# tides2_v40.net
KiCad netlist of a schematic drawn in EAGLE
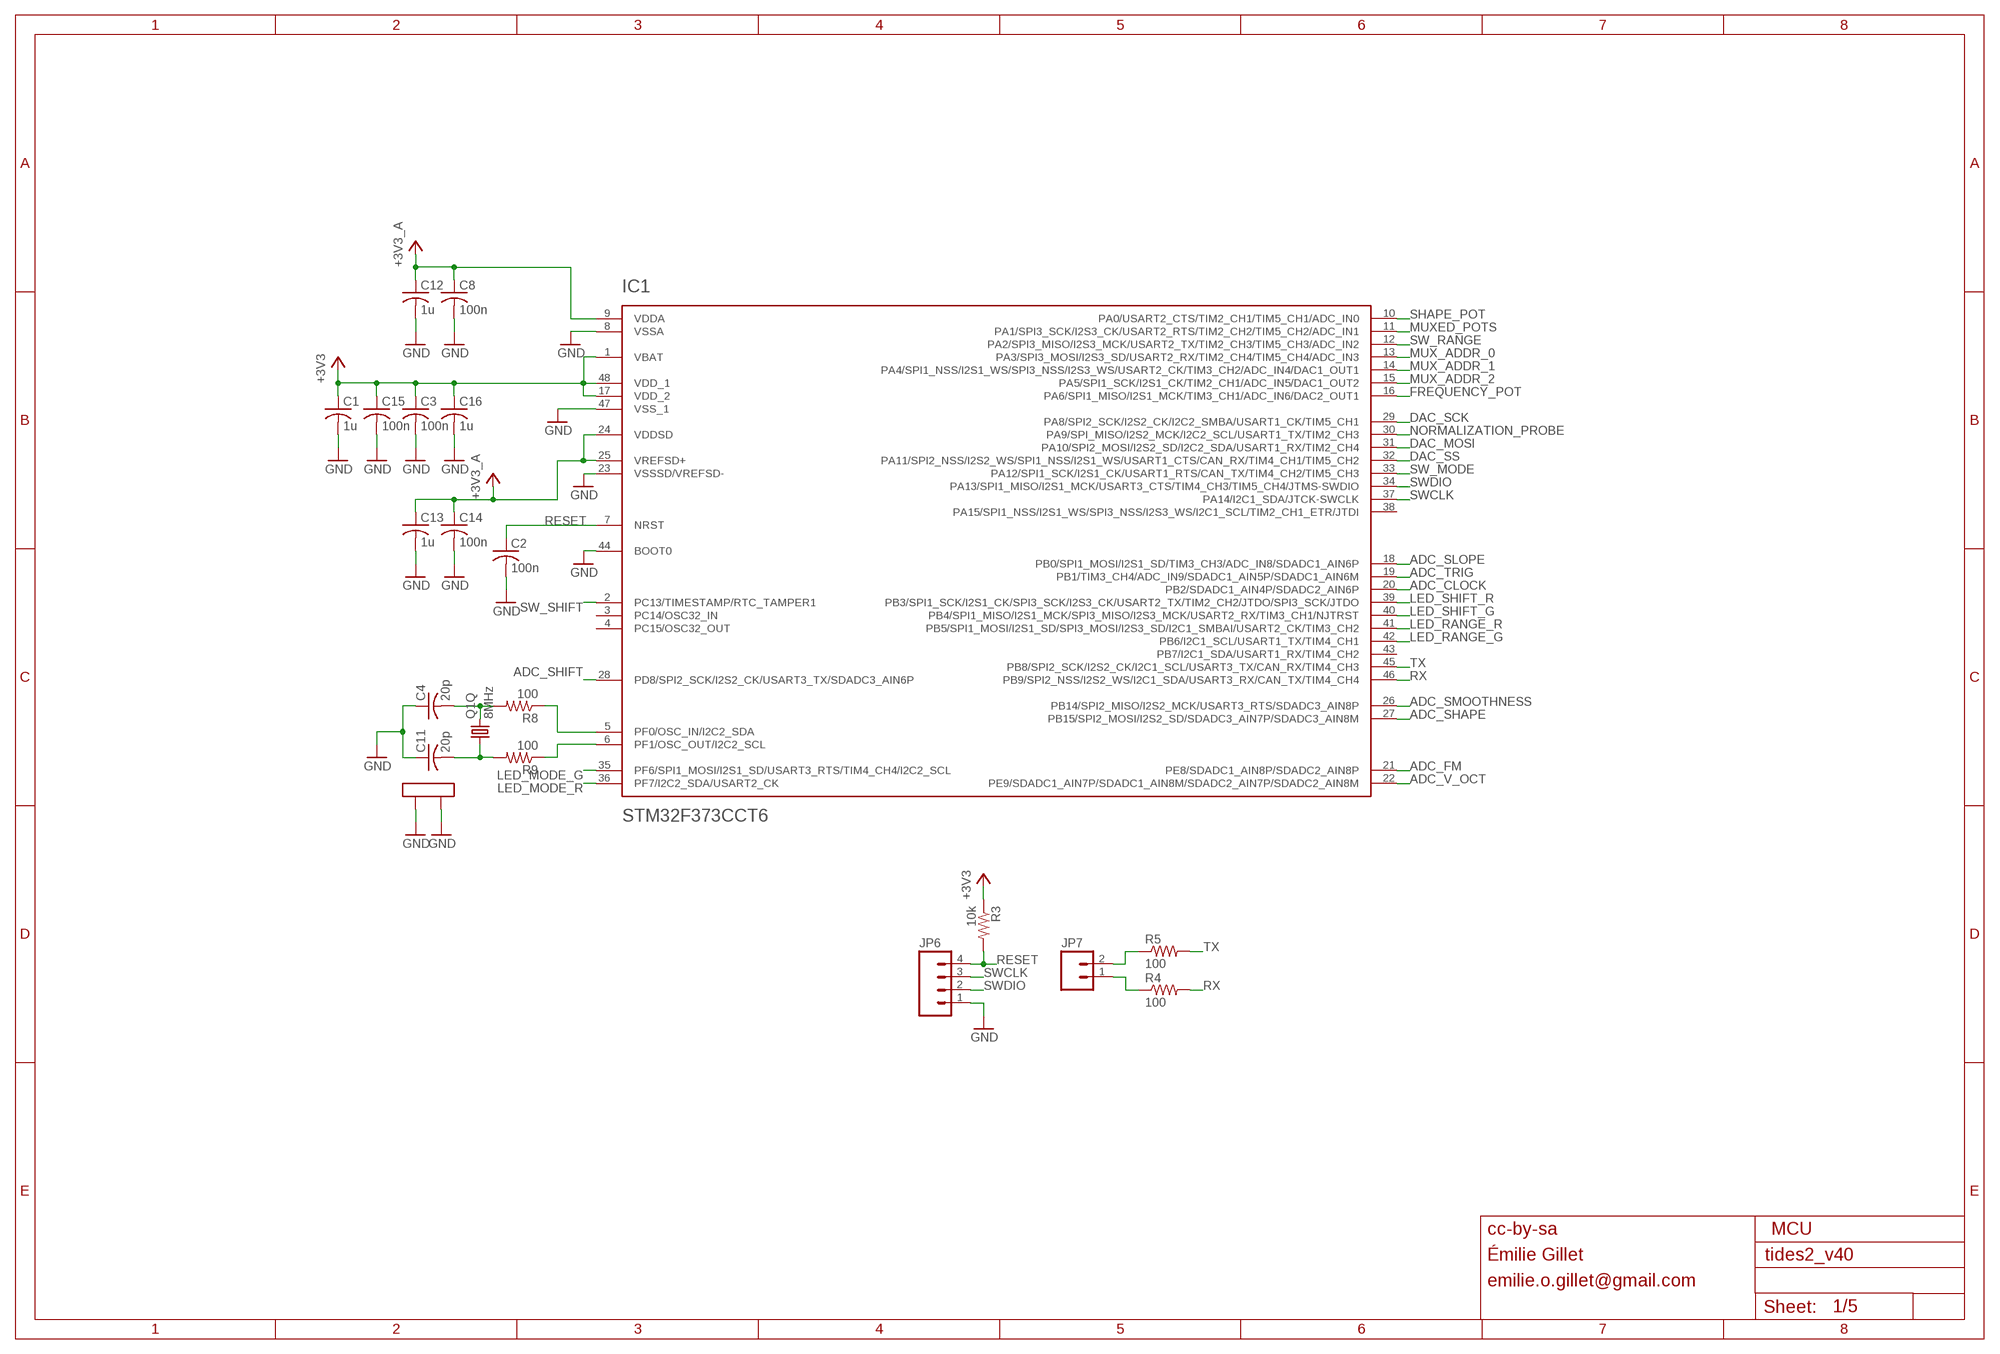
[diagram p0: schematic, sheet 1]
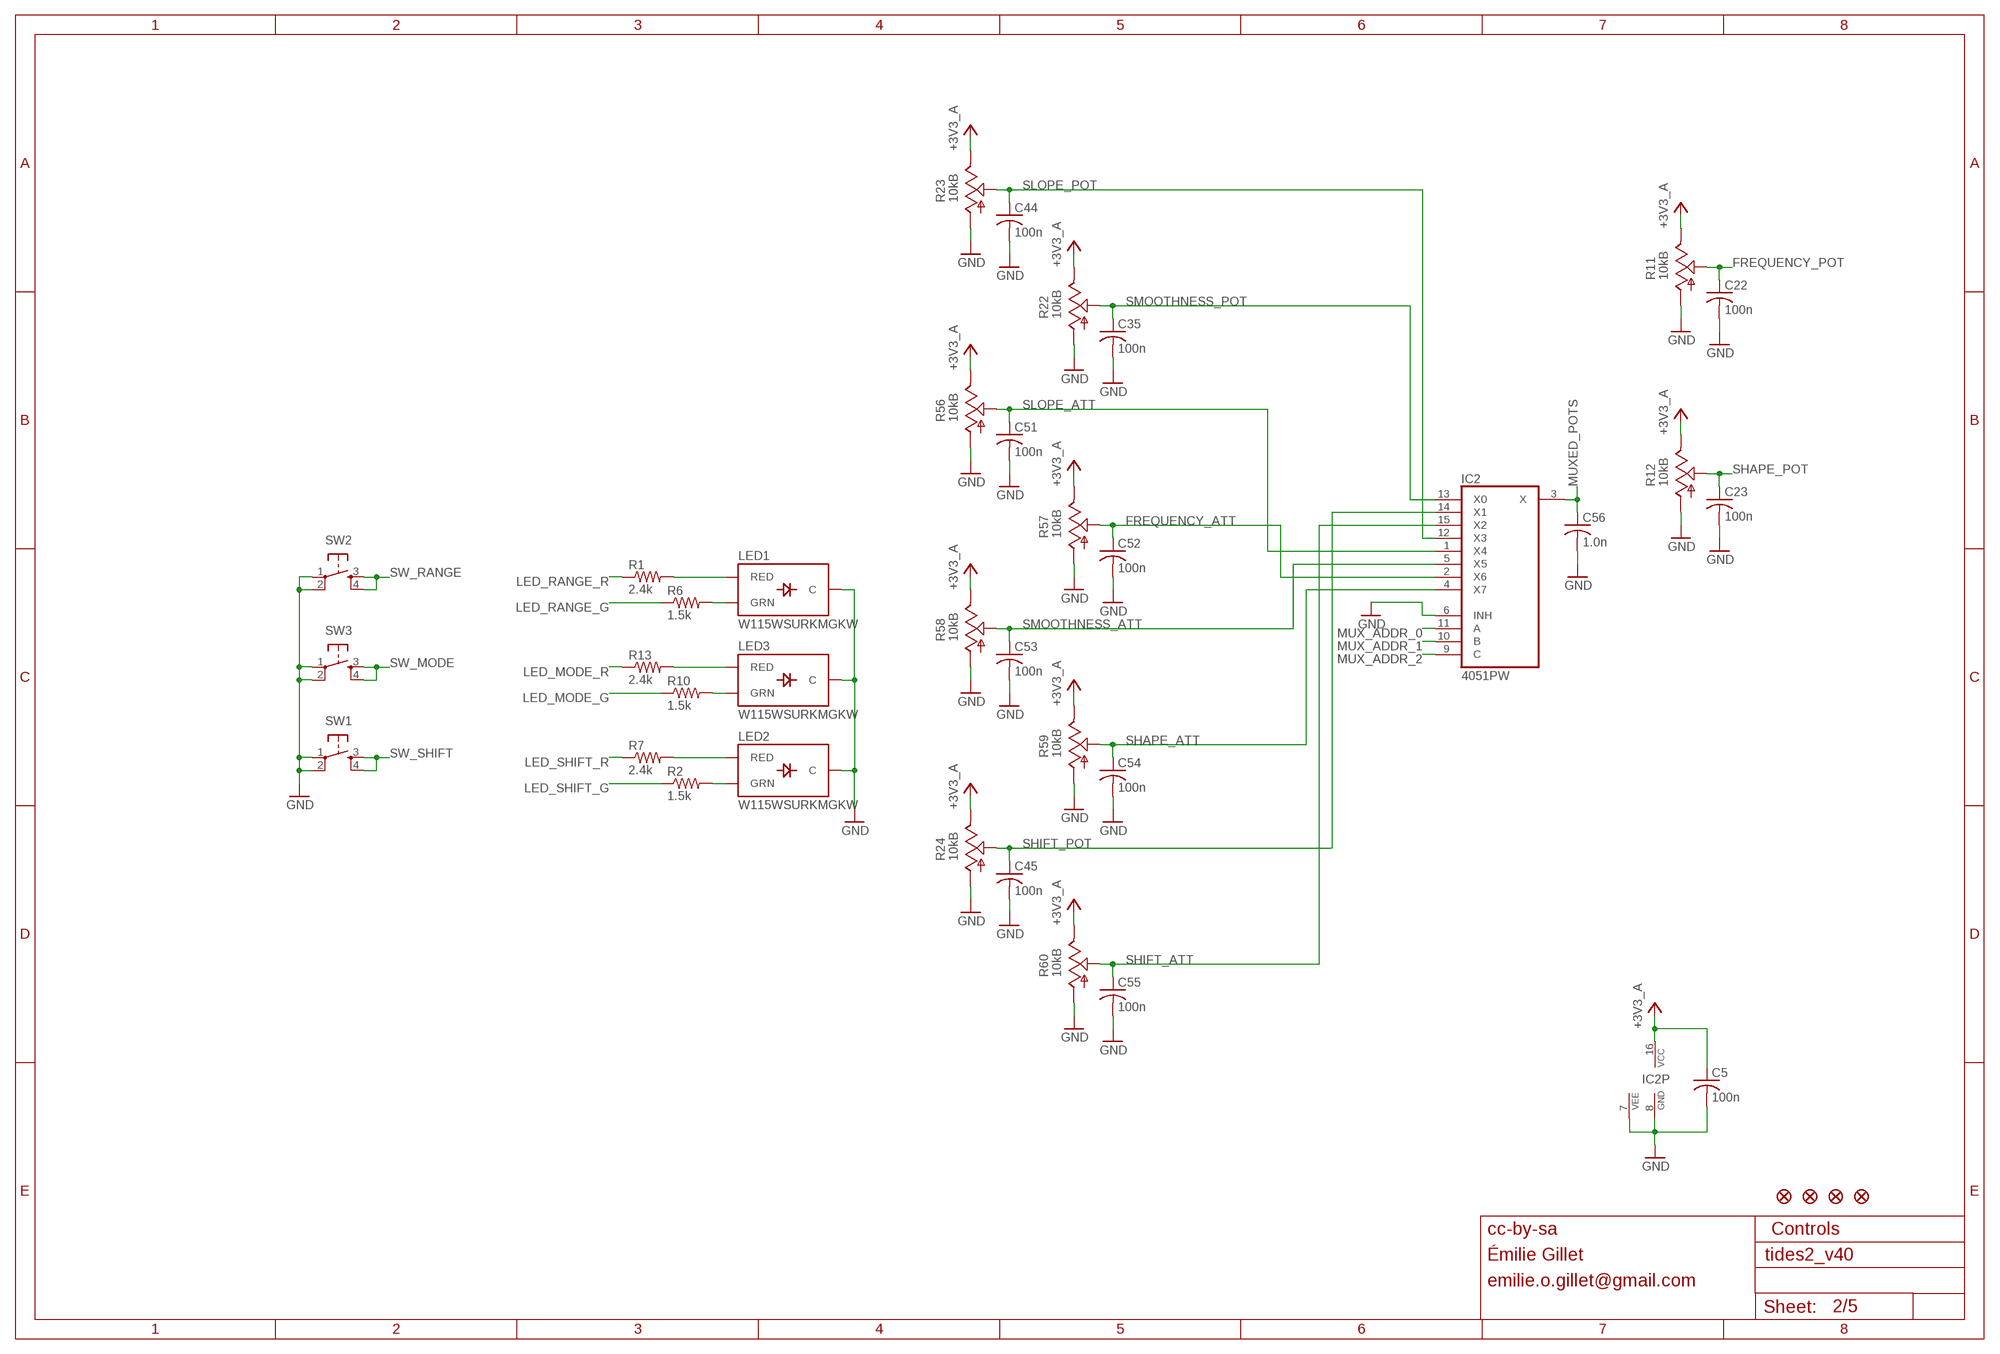
[diagram p1: schematic, sheet 2]
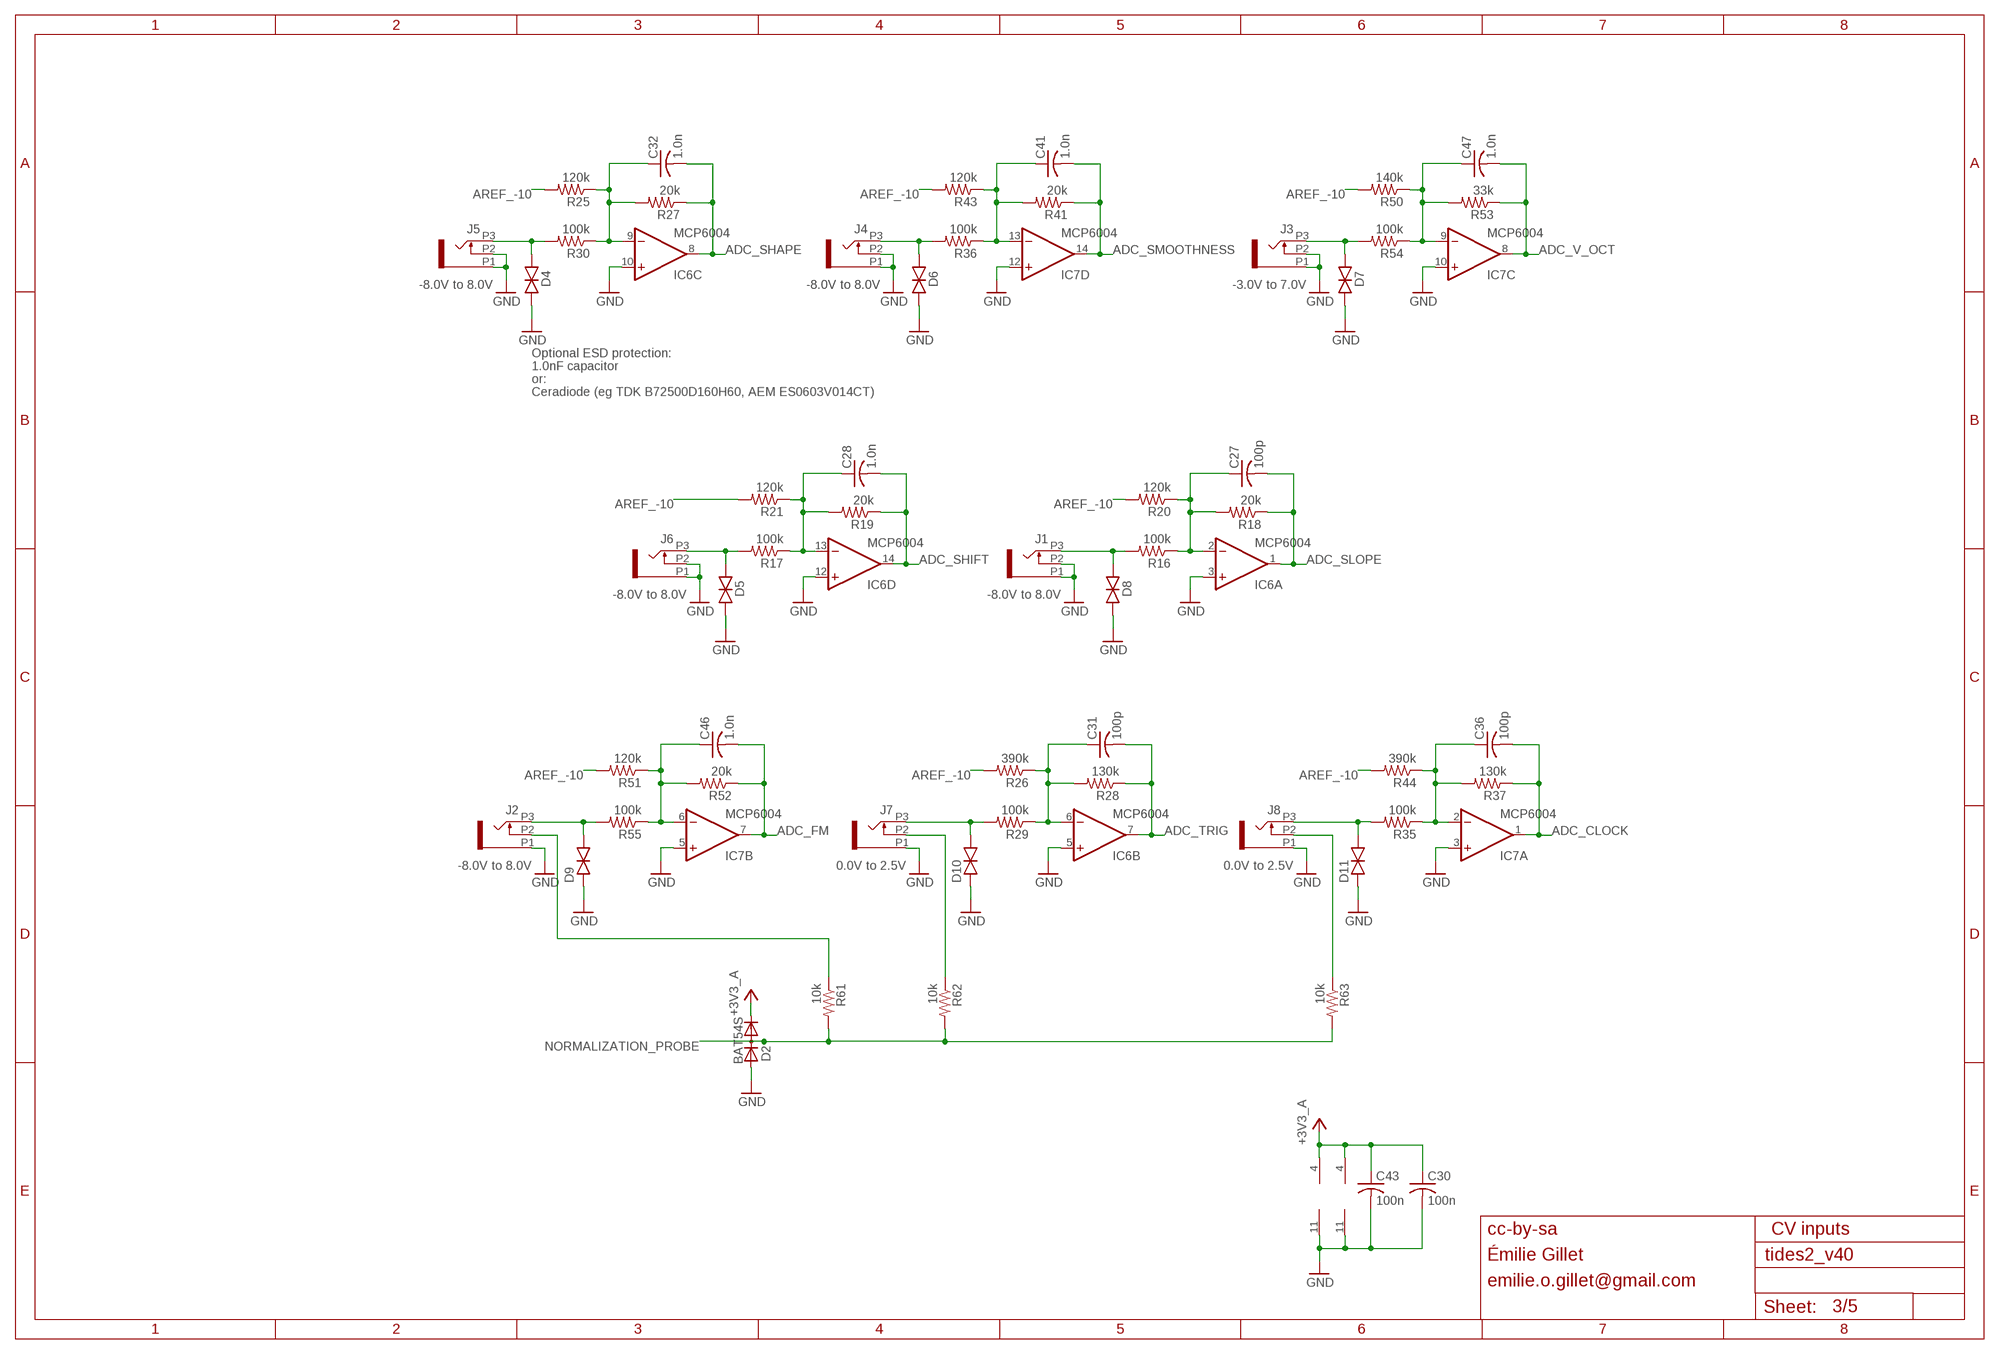
[diagram p2: schematic, sheet 3]
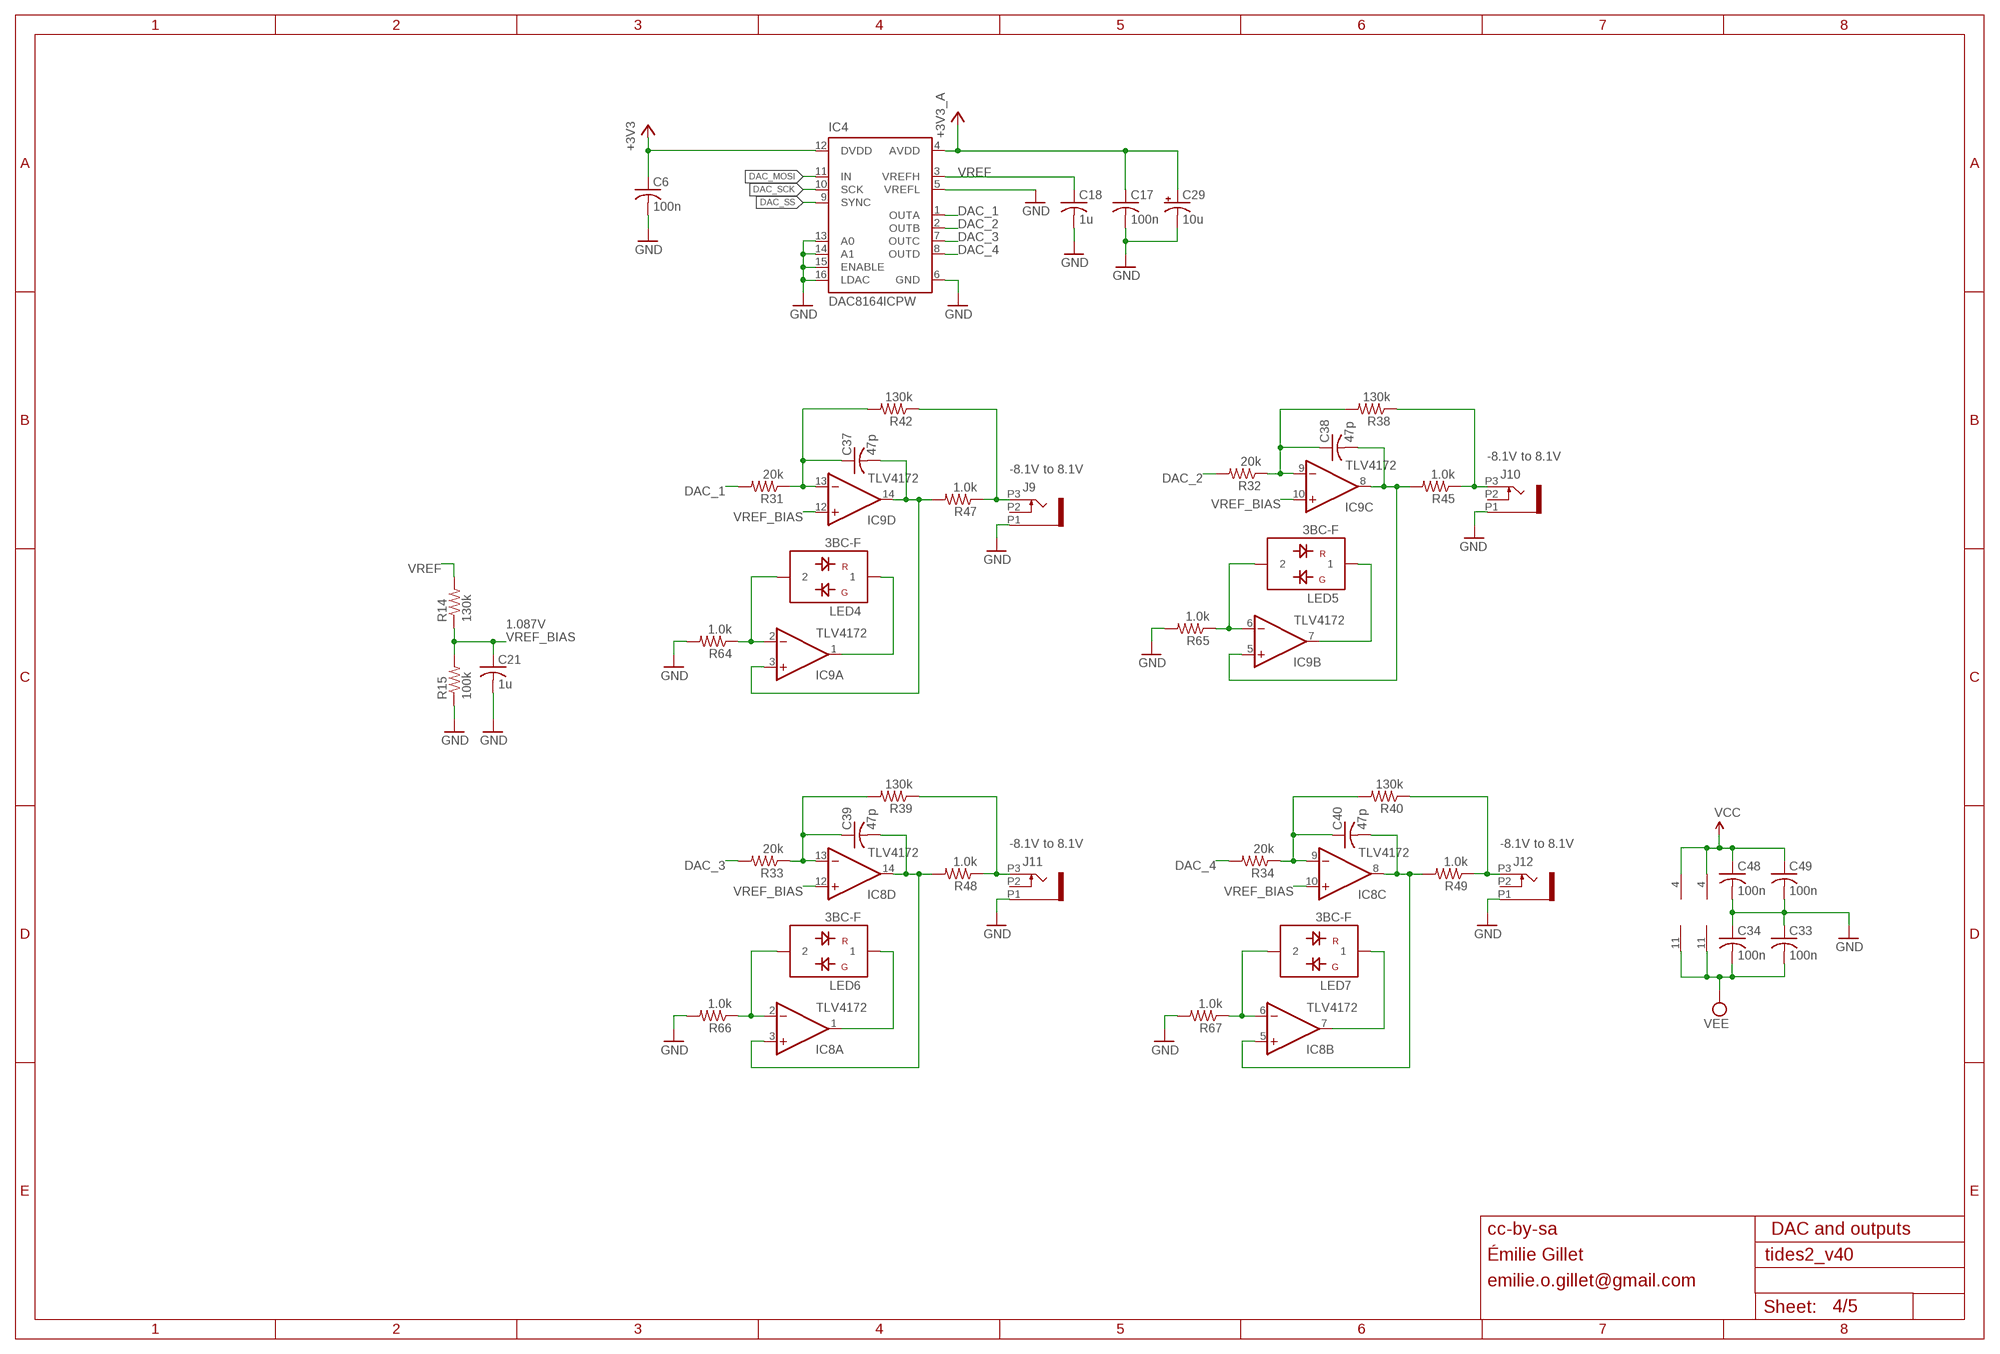
[diagram p3: schematic, sheet 4]
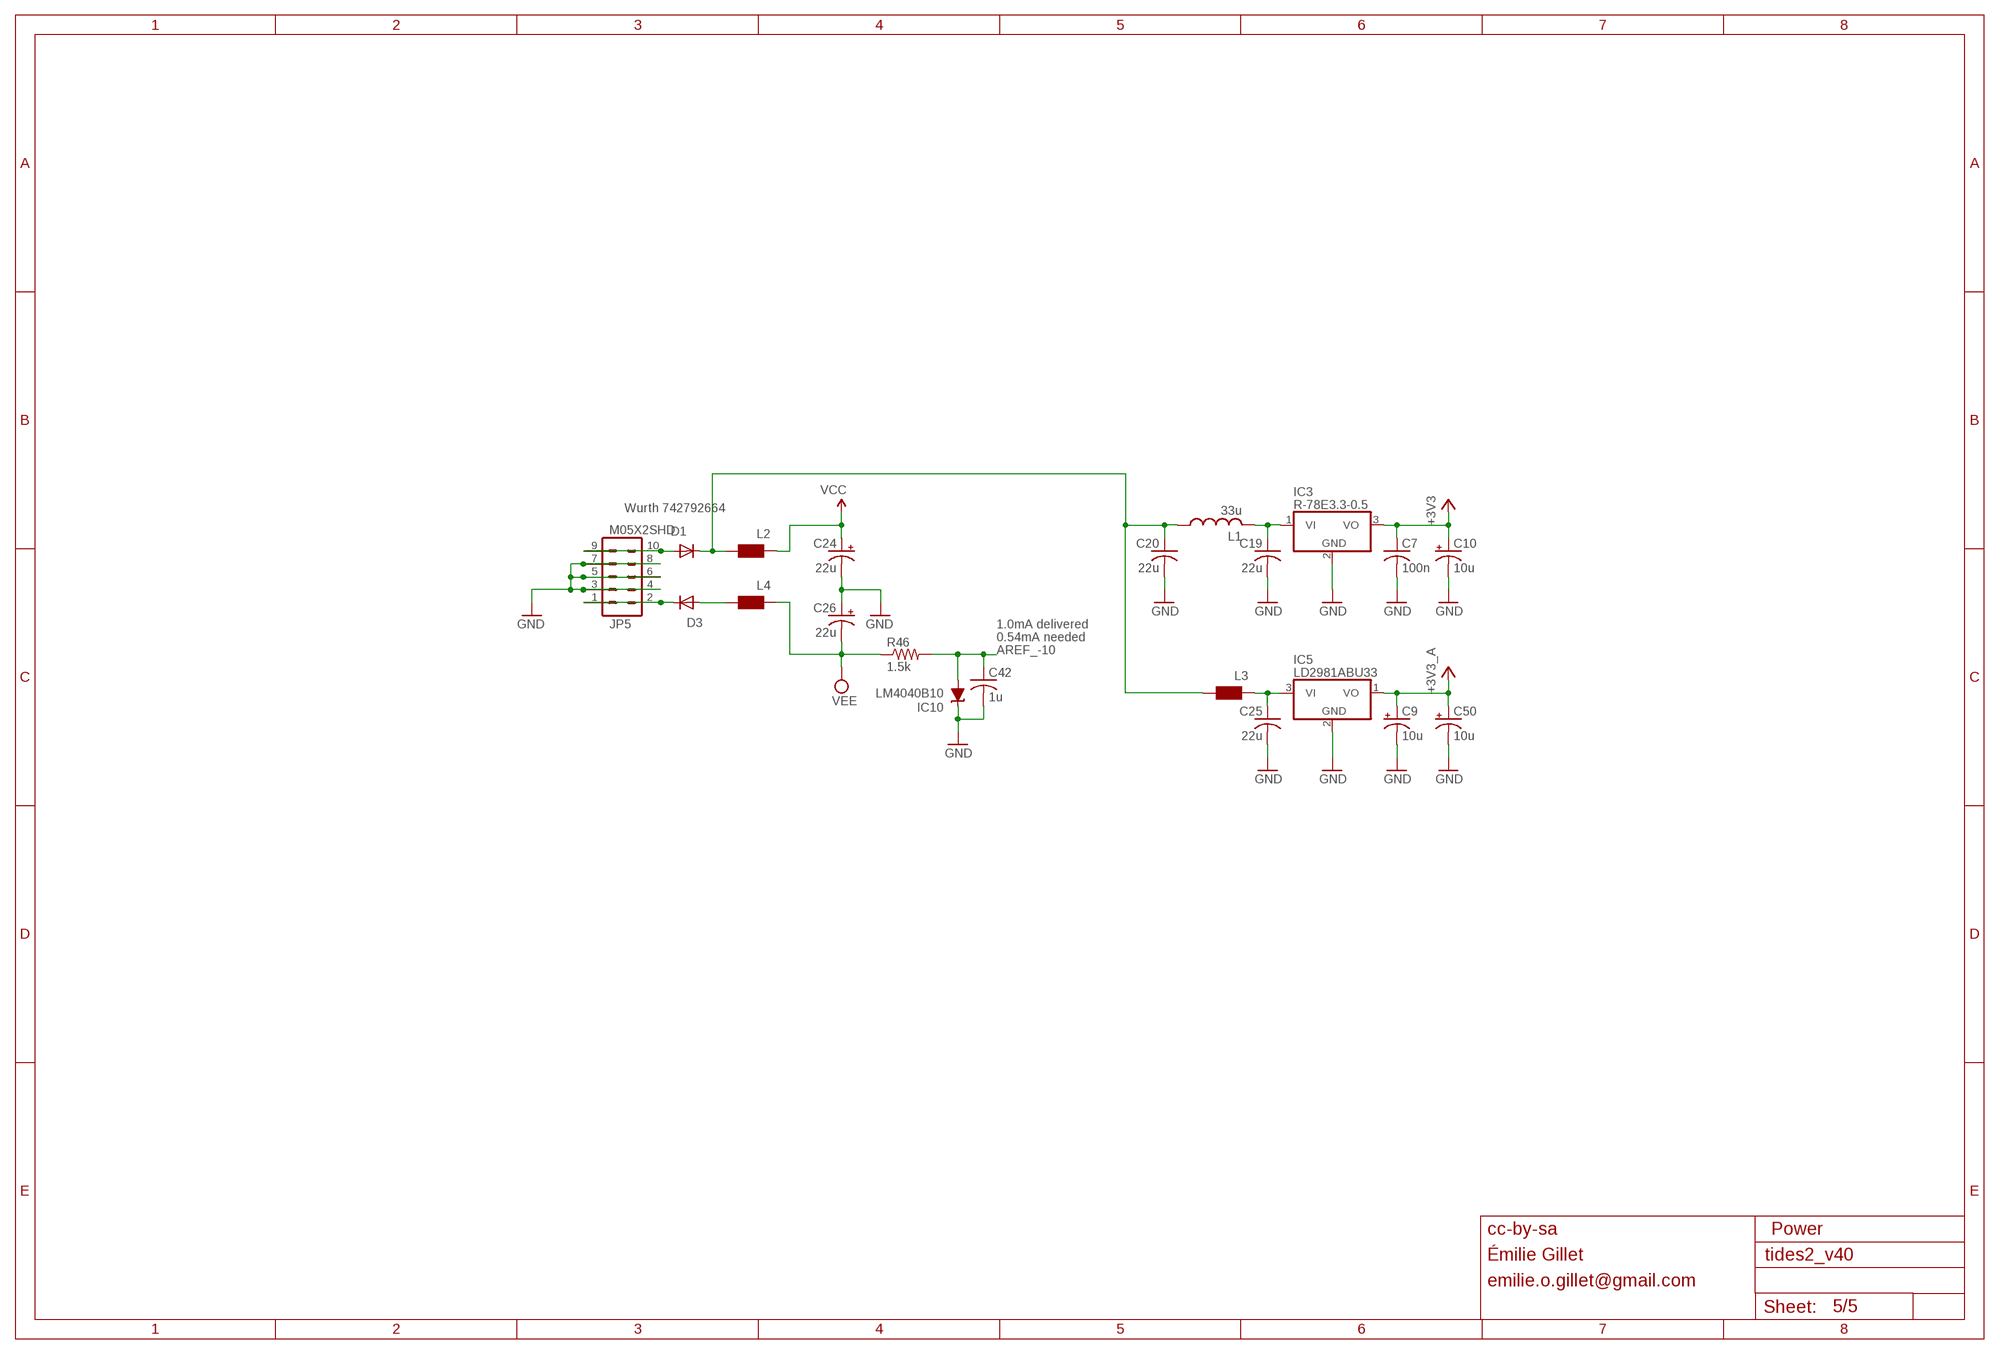
[diagram p4: schematic, sheet 5]

(export (version "E")
  (design (tool "Eeschema 10.0.6"))
  (components
    (comp (ref "C1")
      (value "1u")
      (footprint "eagle-import:C0402")
      (libsource (lib "eagle-import") (part "C-USC0402"))
    )
    (comp (ref "C2")
      (value "100n")
      (footprint "eagle-import:C0402")
      (libsource (lib "eagle-import") (part "C-USC0402"))
    )
    (comp (ref "C3")
      (value "100n")
      (footprint "eagle-import:C0402")
      (libsource (lib "eagle-import") (part "C-USC0402"))
    )
    (comp (ref "C4")
      (value "20p")
      (footprint "eagle-import:C0402")
      (libsource (lib "eagle-import") (part "C-USC0402"))
    )
    (comp (ref "C8")
      (value "100n")
      (footprint "eagle-import:C0402")
      (libsource (lib "eagle-import") (part "C-USC0402"))
    )
    (comp (ref "C11")
      (value "20p")
      (footprint "eagle-import:C0402")
      (libsource (lib "eagle-import") (part "C-USC0402"))
    )
    (comp (ref "C12")
      (value "1u")
      (footprint "eagle-import:C0402")
      (libsource (lib "eagle-import") (part "C-USC0402"))
    )
    (comp (ref "C13")
      (value "1u")
      (footprint "eagle-import:C0402")
      (libsource (lib "eagle-import") (part "C-USC0402"))
    )
    (comp (ref "C14")
      (value "100n")
      (footprint "eagle-import:C0402")
      (libsource (lib "eagle-import") (part "C-USC0402"))
    )
    (comp (ref "C15")
      (value "100n")
      (footprint "eagle-import:C0402")
      (libsource (lib "eagle-import") (part "C-USC0402"))
    )
    (comp (ref "C16")
      (value "1u")
      (footprint "eagle-import:C0402")
      (libsource (lib "eagle-import") (part "C-USC0402"))
    )
    (comp (ref "IC1")
      (value "STM32F373CCT6")
      (footprint "eagle-import:LQFP48")
      (libsource (lib "eagle-import") (part "STM32F373C"))
    )
    (comp (ref "JP6")
      (value "M04PTH")
      (footprint "eagle-import:1X04")
      (libsource (lib "eagle-import") (part "M04PTH"))
    )
    (comp (ref "JP7")
      (value "M02PTH")
      (footprint "eagle-import:1X02")
      (libsource (lib "eagle-import") (part "M02PTH"))
    )
    (comp (ref "Q1")
      (value "8MHz")
      (footprint "eagle-import:CTS406")
      (libsource (lib "eagle-import") (part "CRYSTAL"))
    )
    (comp (ref "R3")
      (value "10k")
      (footprint "eagle-import:R0402")
      (libsource (lib "eagle-import") (part "R-US_R0402"))
    )
    (comp (ref "R4")
      (value "100")
      (footprint "eagle-import:R0402")
      (libsource (lib "eagle-import") (part "R-US_R0402"))
    )
    (comp (ref "R5")
      (value "100")
      (footprint "eagle-import:R0402")
      (libsource (lib "eagle-import") (part "R-US_R0402"))
    )
    (comp (ref "R8")
      (value "100")
      (footprint "eagle-import:R0402")
      (libsource (lib "eagle-import") (part "R-US_R0402"))
    )
    (comp (ref "R9")
      (value "100")
      (footprint "eagle-import:R0402")
      (libsource (lib "eagle-import") (part "R-US_R0402"))
    )
    (comp (ref "C6")
      (value "100n")
      (footprint "eagle-import:C0402")
      (libsource (lib "eagle-import") (part "C-USC0402"))
    )
    (comp (ref "C17")
      (value "100n")
      (footprint "eagle-import:C0402")
      (libsource (lib "eagle-import") (part "C-USC0402"))
    )
    (comp (ref "C18")
      (value "1u")
      (footprint "eagle-import:C0402")
      (libsource (lib "eagle-import") (part "C-USC0402"))
    )
    (comp (ref "C21")
      (value "1u")
      (footprint "eagle-import:C0402")
      (libsource (lib "eagle-import") (part "C-USC0402"))
    )
    (comp (ref "C29")
      (value "10u")
      (footprint "eagle-import:PANASONIC_A")
      (libsource (lib "eagle-import") (part "CPOL-USA"))
    )
    (comp (ref "C33")
      (value "100n")
      (footprint "eagle-import:C0402")
      (libsource (lib "eagle-import") (part "C-USC0402"))
    )
    (comp (ref "C34")
      (value "100n")
      (footprint "eagle-import:C0402")
      (libsource (lib "eagle-import") (part "C-USC0402"))
    )
    (comp (ref "C37")
      (value "47p")
      (footprint "eagle-import:C0402")
      (libsource (lib "eagle-import") (part "C-USC0402"))
    )
    (comp (ref "C38")
      (value "47p")
      (footprint "eagle-import:C0402")
      (libsource (lib "eagle-import") (part "C-USC0402"))
    )
    (comp (ref "C39")
      (value "47p")
      (footprint "eagle-import:C0402")
      (libsource (lib "eagle-import") (part "C-USC0402"))
    )
    (comp (ref "C40")
      (value "47p")
      (footprint "eagle-import:C0402")
      (libsource (lib "eagle-import") (part "C-USC0402"))
    )
    (comp (ref "C48")
      (value "100n")
      (footprint "eagle-import:C0402")
      (libsource (lib "eagle-import") (part "C-USC0402"))
    )
    (comp (ref "C49")
      (value "100n")
      (footprint "eagle-import:C0402")
      (libsource (lib "eagle-import") (part "C-USC0402"))
    )
    (comp (ref "IC4")
      (value "DAC8164ICPW")
      (footprint "eagle-import:SOP65P640X110-16N")
      (libsource (lib "eagle-import") (part "DAC8564"))
    )
    (comp (ref "IC8")
      (value "TLV4172")
      (footprint "eagle-import:TSSOP14_065")
      (libsource (lib "eagle-import") (part "TL074PW"))
    )
    (comp (ref "IC9")
      (value "TLV4172")
      (footprint "eagle-import:TSSOP14_065")
      (libsource (lib "eagle-import") (part "TL074PW"))
    )
    (comp (ref "J9")
      (value "PJ301_THONKICONN6")
      (footprint "eagle-import:WQP_PJ_301M6")
      (libsource (lib "eagle-import") (part "PJ301_THONKICONN6"))
    )
    (comp (ref "J10")
      (value "PJ301_THONKICONN6")
      (footprint "eagle-import:WQP_PJ_301M6")
      (libsource (lib "eagle-import") (part "PJ301_THONKICONN6"))
    )
    (comp (ref "J11")
      (value "PJ301_THONKICONN6")
      (footprint "eagle-import:WQP_PJ_301M6")
      (libsource (lib "eagle-import") (part "PJ301_THONKICONN6"))
    )
    (comp (ref "J12")
      (value "PJ301_THONKICONN6")
      (footprint "eagle-import:WQP_PJ_301M6")
      (libsource (lib "eagle-import") (part "PJ301_THONKICONN6"))
    )
    (comp (ref "LED4")
      (value "3BC-F")
      (footprint "eagle-import:LED3MM")
      (libsource (lib "eagle-import") (part "LED-BICOLOR-SHARED-THROUGHHOLE"))
    )
    (comp (ref "LED5")
      (value "3BC-F")
      (footprint "eagle-import:LED3MM")
      (libsource (lib "eagle-import") (part "LED-BICOLOR-SHARED-THROUGHHOLE"))
    )
    (comp (ref "LED6")
      (value "3BC-F")
      (footprint "eagle-import:LED3MM")
      (libsource (lib "eagle-import") (part "LED-BICOLOR-SHARED-THROUGHHOLE"))
    )
    (comp (ref "LED7")
      (value "3BC-F")
      (footprint "eagle-import:LED3MM")
      (libsource (lib "eagle-import") (part "LED-BICOLOR-SHARED-THROUGHHOLE"))
    )
    (comp (ref "R14")
      (value "130k")
      (footprint "eagle-import:R0402")
      (libsource (lib "eagle-import") (part "R-US_R0402"))
    )
    (comp (ref "R15")
      (value "100k")
      (footprint "eagle-import:R0402")
      (libsource (lib "eagle-import") (part "R-US_R0402"))
    )
    (comp (ref "R31")
      (value "20k")
      (footprint "eagle-import:R0402")
      (libsource (lib "eagle-import") (part "R-US_R0402"))
    )
    (comp (ref "R32")
      (value "20k")
      (footprint "eagle-import:R0402")
      (libsource (lib "eagle-import") (part "R-US_R0402"))
    )
    (comp (ref "R33")
      (value "20k")
      (footprint "eagle-import:R0402")
      (libsource (lib "eagle-import") (part "R-US_R0402"))
    )
    (comp (ref "R34")
      (value "20k")
      (footprint "eagle-import:R0402")
      (libsource (lib "eagle-import") (part "R-US_R0402"))
    )
    (comp (ref "R38")
      (value "130k")
      (footprint "eagle-import:R0402")
      (libsource (lib "eagle-import") (part "R-US_R0402"))
    )
    (comp (ref "R39")
      (value "130k")
      (footprint "eagle-import:R0402")
      (libsource (lib "eagle-import") (part "R-US_R0402"))
    )
    (comp (ref "R40")
      (value "130k")
      (footprint "eagle-import:R0402")
      (libsource (lib "eagle-import") (part "R-US_R0402"))
    )
    (comp (ref "R42")
      (value "130k")
      (footprint "eagle-import:R0402")
      (libsource (lib "eagle-import") (part "R-US_R0402"))
    )
    (comp (ref "R45")
      (value "1.0k")
      (footprint "eagle-import:R0603")
      (libsource (lib "eagle-import") (part "R-US_R0603"))
    )
    (comp (ref "R47")
      (value "1.0k")
      (footprint "eagle-import:R0603")
      (libsource (lib "eagle-import") (part "R-US_R0603"))
    )
    (comp (ref "R48")
      (value "1.0k")
      (footprint "eagle-import:R0603")
      (libsource (lib "eagle-import") (part "R-US_R0603"))
    )
    (comp (ref "R49")
      (value "1.0k")
      (footprint "eagle-import:R0603")
      (libsource (lib "eagle-import") (part "R-US_R0603"))
    )
    (comp (ref "R64")
      (value "1.0k")
      (footprint "eagle-import:R0402")
      (libsource (lib "eagle-import") (part "R-US_R0402"))
    )
    (comp (ref "R65")
      (value "1.0k")
      (footprint "eagle-import:R0402")
      (libsource (lib "eagle-import") (part "R-US_R0402"))
    )
    (comp (ref "R66")
      (value "1.0k")
      (footprint "eagle-import:R0402")
      (libsource (lib "eagle-import") (part "R-US_R0402"))
    )
    (comp (ref "R67")
      (value "1.0k")
      (footprint "eagle-import:R0402")
      (libsource (lib "eagle-import") (part "R-US_R0402"))
    )
    (comp (ref "C27")
      (value "100p")
      (footprint "eagle-import:C0402")
      (libsource (lib "eagle-import") (part "C-USC0402"))
    )
    (comp (ref "C28")
      (value "1.0n")
      (footprint "eagle-import:C0402")
      (libsource (lib "eagle-import") (part "C-USC0402"))
    )
    (comp (ref "C30")
      (value "100n")
      (footprint "eagle-import:C0402")
      (libsource (lib "eagle-import") (part "C-USC0402"))
    )
    (comp (ref "C31")
      (value "100p")
      (footprint "eagle-import:C0402")
      (libsource (lib "eagle-import") (part "C-USC0402"))
    )
    (comp (ref "C32")
      (value "1.0n")
      (footprint "eagle-import:C0402")
      (libsource (lib "eagle-import") (part "C-USC0402"))
    )
    (comp (ref "C36")
      (value "100p")
      (footprint "eagle-import:C0402")
      (libsource (lib "eagle-import") (part "C-USC0402"))
    )
    (comp (ref "C41")
      (value "1.0n")
      (footprint "eagle-import:C0402")
      (libsource (lib "eagle-import") (part "C-USC0402"))
    )
    (comp (ref "C43")
      (value "100n")
      (footprint "eagle-import:C0402")
      (libsource (lib "eagle-import") (part "C-USC0402"))
    )
    (comp (ref "C46")
      (value "1.0n")
      (footprint "eagle-import:C0402")
      (libsource (lib "eagle-import") (part "C-USC0402"))
    )
    (comp (ref "C47")
      (value "1.0n")
      (footprint "eagle-import:C0402")
      (libsource (lib "eagle-import") (part "C-USC0402"))
    )
    (comp (ref "D2")
      (value "BAT54S")
      (footprint "eagle-import:SOT23")
      (libsource (lib "eagle-import") (part "DIODE_2CACA-SOT23"))
    )
    (comp (ref "D4")
      (value "TVS")
      (footprint "eagle-import:0603")
      (libsource (lib "eagle-import") (part "TVS"))
    )
    (comp (ref "D5")
      (value "TVS")
      (footprint "eagle-import:0603")
      (libsource (lib "eagle-import") (part "TVS"))
    )
    (comp (ref "D6")
      (value "TVS")
      (footprint "eagle-import:0603")
      (libsource (lib "eagle-import") (part "TVS"))
    )
    (comp (ref "D7")
      (value "TVS")
      (footprint "eagle-import:0603")
      (libsource (lib "eagle-import") (part "TVS"))
    )
    (comp (ref "D8")
      (value "TVS")
      (footprint "eagle-import:0603")
      (libsource (lib "eagle-import") (part "TVS"))
    )
    (comp (ref "D9")
      (value "TVS")
      (footprint "eagle-import:0603")
      (libsource (lib "eagle-import") (part "TVS"))
    )
    (comp (ref "D10")
      (value "TVS")
      (footprint "eagle-import:0603")
      (libsource (lib "eagle-import") (part "TVS"))
    )
    (comp (ref "D11")
      (value "TVS")
      (footprint "eagle-import:0603")
      (libsource (lib "eagle-import") (part "TVS"))
    )
    (comp (ref "IC6")
      (value "MCP6004")
      (footprint "eagle-import:TSSOP14_065")
      (libsource (lib "eagle-import") (part "TL074PW"))
    )
    (comp (ref "IC7")
      (value "MCP6004")
      (footprint "eagle-import:TSSOP14_065")
      (libsource (lib "eagle-import") (part "TL074PW"))
    )
    (comp (ref "J1")
      (value "PJ301_THONKICONN6")
      (footprint "eagle-import:WQP_PJ_301M6")
      (libsource (lib "eagle-import") (part "og-pj301_variations_PJ301_THONKICONN6"))
    )
    (comp (ref "J2")
      (value "PJ301_THONKICONN6")
      (footprint "eagle-import:WQP_PJ_301M6")
      (libsource (lib "eagle-import") (part "og-pj301_variations_PJ301_THONKICONN6"))
    )
    (comp (ref "J3")
      (value "PJ301_THONKICONN6")
      (footprint "eagle-import:WQP_PJ_301M6")
      (libsource (lib "eagle-import") (part "og-pj301_variations_PJ301_THONKICONN6"))
    )
    (comp (ref "J4")
      (value "PJ301_THONKICONN6")
      (footprint "eagle-import:WQP_PJ_301M6")
      (libsource (lib "eagle-import") (part "og-pj301_variations_PJ301_THONKICONN6"))
    )
    (comp (ref "J5")
      (value "PJ301_THONKICONN6")
      (footprint "eagle-import:WQP_PJ_301M6")
      (libsource (lib "eagle-import") (part "og-pj301_variations_PJ301_THONKICONN6"))
    )
    (comp (ref "J6")
      (value "PJ301_THONKICONN6")
      (footprint "eagle-import:WQP_PJ_301M6")
      (libsource (lib "eagle-import") (part "og-pj301_variations_PJ301_THONKICONN6"))
    )
    (comp (ref "J7")
      (value "PJ301_THONKICONN6")
      (footprint "eagle-import:WQP_PJ_301M6")
      (libsource (lib "eagle-import") (part "og-pj301_variations_PJ301_THONKICONN6"))
    )
    (comp (ref "J8")
      (value "PJ301_THONKICONN6")
      (footprint "eagle-import:WQP_PJ_301M6")
      (libsource (lib "eagle-import") (part "og-pj301_variations_PJ301_THONKICONN6"))
    )
    (comp (ref "R16")
      (value "100k")
      (footprint "eagle-import:R0402")
      (libsource (lib "eagle-import") (part "R-US_R0402"))
    )
    (comp (ref "R17")
      (value "100k")
      (footprint "eagle-import:R0402")
      (libsource (lib "eagle-import") (part "R-US_R0402"))
    )
    (comp (ref "R18")
      (value "20k")
      (footprint "eagle-import:R0402")
      (libsource (lib "eagle-import") (part "R-US_R0402"))
    )
    (comp (ref "R19")
      (value "20k")
      (footprint "eagle-import:R0402")
      (libsource (lib "eagle-import") (part "R-US_R0402"))
    )
    (comp (ref "R20")
      (value "120k")
      (footprint "eagle-import:R0402")
      (libsource (lib "eagle-import") (part "R-US_R0402"))
    )
    (comp (ref "R21")
      (value "120k")
      (footprint "eagle-import:R0402")
      (libsource (lib "eagle-import") (part "R-US_R0402"))
    )
    (comp (ref "R25")
      (value "120k")
      (footprint "eagle-import:R0402")
      (libsource (lib "eagle-import") (part "R-US_R0402"))
    )
    (comp (ref "R26")
      (value "390k")
      (footprint "eagle-import:R0402")
      (libsource (lib "eagle-import") (part "R-US_R0402"))
    )
    (comp (ref "R27")
      (value "20k")
      (footprint "eagle-import:R0402")
      (libsource (lib "eagle-import") (part "R-US_R0402"))
    )
    (comp (ref "R28")
      (value "130k")
      (footprint "eagle-import:R0402")
      (libsource (lib "eagle-import") (part "R-US_R0402"))
    )
    (comp (ref "R29")
      (value "100k")
      (footprint "eagle-import:R0402")
      (libsource (lib "eagle-import") (part "R-US_R0402"))
    )
    (comp (ref "R30")
      (value "100k")
      (footprint "eagle-import:R0402")
      (libsource (lib "eagle-import") (part "R-US_R0402"))
    )
    (comp (ref "R35")
      (value "100k")
      (footprint "eagle-import:R0402")
      (libsource (lib "eagle-import") (part "R-US_R0402"))
    )
    (comp (ref "R36")
      (value "100k")
      (footprint "eagle-import:R0402")
      (libsource (lib "eagle-import") (part "R-US_R0402"))
    )
    (comp (ref "R37")
      (value "130k")
      (footprint "eagle-import:R0402")
      (libsource (lib "eagle-import") (part "R-US_R0402"))
    )
    (comp (ref "R41")
      (value "20k")
      (footprint "eagle-import:R0402")
      (libsource (lib "eagle-import") (part "R-US_R0402"))
    )
    (comp (ref "R43")
      (value "120k")
      (footprint "eagle-import:R0402")
      (libsource (lib "eagle-import") (part "R-US_R0402"))
    )
    (comp (ref "R44")
      (value "390k")
      (footprint "eagle-import:R0402")
      (libsource (lib "eagle-import") (part "R-US_R0402"))
    )
    (comp (ref "R50")
      (value "140k")
      (footprint "eagle-import:R0402")
      (libsource (lib "eagle-import") (part "R-US_R0402"))
    )
    (comp (ref "R51")
      (value "120k")
      (footprint "eagle-import:R0402")
      (libsource (lib "eagle-import") (part "R-US_R0402"))
    )
    (comp (ref "R52")
      (value "20k")
      (footprint "eagle-import:R0402")
      (libsource (lib "eagle-import") (part "R-US_R0402"))
    )
    (comp (ref "R53")
      (value "33k")
      (footprint "eagle-import:R0402")
      (libsource (lib "eagle-import") (part "R-US_R0402"))
    )
    (comp (ref "R54")
      (value "100k")
      (footprint "eagle-import:R0402")
      (libsource (lib "eagle-import") (part "R-US_R0402"))
    )
    (comp (ref "R55")
      (value "100k")
      (footprint "eagle-import:R0402")
      (libsource (lib "eagle-import") (part "R-US_R0402"))
    )
    (comp (ref "R61")
      (value "10k")
      (footprint "eagle-import:R0402")
      (libsource (lib "eagle-import") (part "R-US_R0402"))
    )
    (comp (ref "R62")
      (value "10k")
      (footprint "eagle-import:R0402")
      (libsource (lib "eagle-import") (part "R-US_R0402"))
    )
    (comp (ref "R63")
      (value "10k")
      (footprint "eagle-import:R0402")
      (libsource (lib "eagle-import") (part "R-US_R0402"))
    )
    (comp (ref "C7")
      (value "100n")
      (footprint "eagle-import:C0402")
      (libsource (lib "eagle-import") (part "C-USC0402"))
    )
    (comp (ref "C9")
      (value "10u")
      (footprint "eagle-import:PANASONIC_A")
      (libsource (lib "eagle-import") (part "CPOL-USA"))
    )
    (comp (ref "C10")
      (value "10u")
      (footprint "eagle-import:PANASONIC_A")
      (libsource (lib "eagle-import") (part "CPOL-USA"))
    )
    (comp (ref "C19")
      (value "22u")
      (footprint "eagle-import:C1206")
      (libsource (lib "eagle-import") (part "C-USC1206"))
    )
    (comp (ref "C20")
      (value "22u")
      (footprint "eagle-import:C1206")
      (libsource (lib "eagle-import") (part "C-USC1206"))
    )
    (comp (ref "C24")
      (value "22u")
      (footprint "eagle-import:PANASONIC_B")
      (libsource (lib "eagle-import") (part "CPOL-USB"))
    )
    (comp (ref "C25")
      (value "22u")
      (footprint "eagle-import:C1206")
      (libsource (lib "eagle-import") (part "C-USC1206"))
    )
    (comp (ref "C26")
      (value "22u")
      (footprint "eagle-import:PANASONIC_B")
      (libsource (lib "eagle-import") (part "CPOL-USB"))
    )
    (comp (ref "C42")
      (value "1u")
      (footprint "eagle-import:C0402")
      (libsource (lib "eagle-import") (part "C-USC0402"))
    )
    (comp (ref "C50")
      (value "10u")
      (footprint "eagle-import:PANASONIC_A")
      (libsource (lib "eagle-import") (part "CPOL-USA"))
    )
    (comp (ref "D1")
      (value "1N5819HW")
      (footprint "eagle-import:SOD123")
      (libsource (lib "eagle-import") (part "DIODE-SOD123"))
    )
    (comp (ref "D3")
      (value "1N5819HW")
      (footprint "eagle-import:SOD123")
      (libsource (lib "eagle-import") (part "DIODE-SOD123"))
    )
    (comp (ref "IC3")
      (value "R-78E3.3-0.5")
      (footprint "eagle-import:WE78")
      (libsource (lib "eagle-import") (part "WE173950378"))
    )
    (comp (ref "IC5")
      (value "LD2981ABU33")
      (footprint "eagle-import:SOT89")
      (libsource (lib "eagle-import") (part "LD2981ABU"))
    )
    (comp (ref "IC10")
      (value "LM4040B10")
      (footprint "eagle-import:DBZ_R-PDSO-G3")
      (libsource (lib "eagle-import") (part "LM4041DBZB12"))
    )
    (comp (ref "JP5")
      (value "M05X2SHD")
      (footprint "eagle-import:2X5-SHROUDED")
      (libsource (lib "eagle-import") (part "M05X2SHD"))
    )
    (comp (ref "L1")
      (value "33u")
      (footprint "eagle-import:L2012C")
      (libsource (lib "eagle-import") (part "L-USL2012C"))
    )
    (comp (ref "L2")
      (value "WE-CBF_0603")
      (footprint "eagle-import:0603")
      (libsource (lib "eagle-import") (part "WE-CBF_0603"))
    )
    (comp (ref "L3")
      (value "WE-CBF_0603")
      (footprint "eagle-import:0603")
      (libsource (lib "eagle-import") (part "WE-CBF_0603"))
    )
    (comp (ref "L4")
      (value "WE-CBF_0603")
      (footprint "eagle-import:0603")
      (libsource (lib "eagle-import") (part "WE-CBF_0603"))
    )
    (comp (ref "R46")
      (value "1.5k")
      (footprint "eagle-import:R0402")
      (libsource (lib "eagle-import") (part "R-US_R0402"))
    )
    (comp (ref "C5")
      (value "100n")
      (footprint "eagle-import:C0402")
      (libsource (lib "eagle-import") (part "C-USC0402"))
    )
    (comp (ref "C22")
      (value "100n")
      (footprint "eagle-import:C0402")
      (libsource (lib "eagle-import") (part "C-USC0402"))
    )
    (comp (ref "C23")
      (value "100n")
      (footprint "eagle-import:C0402")
      (libsource (lib "eagle-import") (part "C-USC0402"))
    )
    (comp (ref "C35")
      (value "100n")
      (footprint "eagle-import:C0402")
      (libsource (lib "eagle-import") (part "C-USC0402"))
    )
    (comp (ref "C44")
      (value "100n")
      (footprint "eagle-import:C0402")
      (libsource (lib "eagle-import") (part "C-USC0402"))
    )
    (comp (ref "C45")
      (value "100n")
      (footprint "eagle-import:C0402")
      (libsource (lib "eagle-import") (part "C-USC0402"))
    )
    (comp (ref "C51")
      (value "100n")
      (footprint "eagle-import:C0402")
      (libsource (lib "eagle-import") (part "C-USC0402"))
    )
    (comp (ref "C52")
      (value "100n")
      (footprint "eagle-import:C0402")
      (libsource (lib "eagle-import") (part "C-USC0402"))
    )
    (comp (ref "C53")
      (value "100n")
      (footprint "eagle-import:C0402")
      (libsource (lib "eagle-import") (part "C-USC0402"))
    )
    (comp (ref "C54")
      (value "100n")
      (footprint "eagle-import:C0402")
      (libsource (lib "eagle-import") (part "C-USC0402"))
    )
    (comp (ref "C55")
      (value "100n")
      (footprint "eagle-import:C0402")
      (libsource (lib "eagle-import") (part "C-USC0402"))
    )
    (comp (ref "C56")
      (value "1.0n")
      (footprint "eagle-import:C0402")
      (libsource (lib "eagle-import") (part "C-USC0402"))
    )
    (comp (ref "IC2")
      (value "4051PW")
      (footprint "eagle-import:TSSOP16_065")
      (libsource (lib "eagle-import") (part "4051PW"))
    )
    (comp (ref "JP1")
      (value "FIDUCIAL1X2")
      (footprint "eagle-import:FIDUCIAL-1X2")
      (libsource (lib "eagle-import") (part "FIDUCIAL1X2"))
    )
    (comp (ref "JP2")
      (value "FIDUCIAL1X2")
      (footprint "eagle-import:FIDUCIAL-1X2")
      (libsource (lib "eagle-import") (part "FIDUCIAL1X2"))
    )
    (comp (ref "JP3")
      (value "FIDUCIAL1X2")
      (footprint "eagle-import:FIDUCIAL-1X2")
      (libsource (lib "eagle-import") (part "FIDUCIAL1X2"))
    )
    (comp (ref "JP4")
      (value "FIDUCIAL1X2")
      (footprint "eagle-import:FIDUCIAL-1X2")
      (libsource (lib "eagle-import") (part "FIDUCIAL1X2"))
    )
    (comp (ref "LED1")
      (value "W115WSURKMGKW")
      (footprint "eagle-import:LED-BICOLOR-THROUGHHOLE-2.54")
      (libsource (lib "eagle-import") (part "LED-BICOLOR-THROUGHHOLE2.54"))
    )
    (comp (ref "LED2")
      (value "W115WSURKMGKW")
      (footprint "eagle-import:LED-BICOLOR-THROUGHHOLE-2.54")
      (libsource (lib "eagle-import") (part "LED-BICOLOR-THROUGHHOLE2.54"))
    )
    (comp (ref "LED3")
      (value "W115WSURKMGKW")
      (footprint "eagle-import:LED-BICOLOR-THROUGHHOLE-2.54")
      (libsource (lib "eagle-import") (part "LED-BICOLOR-THROUGHHOLE2.54"))
    )
    (comp (ref "R1")
      (value "2.4k")
      (footprint "eagle-import:R0402")
      (libsource (lib "eagle-import") (part "R-US_R0402"))
    )
    (comp (ref "R2")
      (value "1.5k")
      (footprint "eagle-import:R0402")
      (libsource (lib "eagle-import") (part "R-US_R0402"))
    )
    (comp (ref "R6")
      (value "1.5k")
      (footprint "eagle-import:R0402")
      (libsource (lib "eagle-import") (part "R-US_R0402"))
    )
    (comp (ref "R7")
      (value "2.4k")
      (footprint "eagle-import:R0402")
      (libsource (lib "eagle-import") (part "R-US_R0402"))
    )
    (comp (ref "R10")
      (value "1.5k")
      (footprint "eagle-import:R0402")
      (libsource (lib "eagle-import") (part "R-US_R0402"))
    )
    (comp (ref "R11")
      (value "10kB")
      (footprint "eagle-import:ALPS_POT_VERTICAL_PS")
      (libsource (lib "eagle-import") (part "POT_USVERTICAL_PS"))
    )
    (comp (ref "R12")
      (value "10kB")
      (footprint "eagle-import:ALPS_POT_VERTICAL_PS")
      (libsource (lib "eagle-import") (part "POT_USVERTICAL_PS"))
    )
    (comp (ref "R13")
      (value "2.4k")
      (footprint "eagle-import:R0402")
      (libsource (lib "eagle-import") (part "R-US_R0402"))
    )
    (comp (ref "R22")
      (value "10kB")
      (footprint "eagle-import:ALPS_POT_VERTICAL_PS")
      (libsource (lib "eagle-import") (part "POT_USVERTICAL_PS"))
    )
    (comp (ref "R23")
      (value "10kB")
      (footprint "eagle-import:ALPS_POT_VERTICAL_PS")
      (libsource (lib "eagle-import") (part "POT_USVERTICAL_PS"))
    )
    (comp (ref "R24")
      (value "10kB")
      (footprint "eagle-import:ALPS_POT_VERTICAL_PS")
      (libsource (lib "eagle-import") (part "POT_USVERTICAL_PS"))
    )
    (comp (ref "R56")
      (value "10kB")
      (footprint "eagle-import:ALPS_POT_VERTICAL")
      (libsource (lib "eagle-import") (part "POT_USVERTICAL"))
    )
    (comp (ref "R57")
      (value "10kB")
      (footprint "eagle-import:ALPS_POT_VERTICAL")
      (libsource (lib "eagle-import") (part "POT_USVERTICAL"))
    )
    (comp (ref "R58")
      (value "10kB")
      (footprint "eagle-import:ALPS_POT_VERTICAL")
      (libsource (lib "eagle-import") (part "POT_USVERTICAL"))
    )
    (comp (ref "R59")
      (value "10kB")
      (footprint "eagle-import:ALPS_POT_VERTICAL")
      (libsource (lib "eagle-import") (part "POT_USVERTICAL"))
    )
    (comp (ref "R60")
      (value "10kB")
      (footprint "eagle-import:ALPS_POT_VERTICAL")
      (libsource (lib "eagle-import") (part "POT_USVERTICAL"))
    )
    (comp (ref "SW1")
      (value "TAC_SWITCHPTH")
      (footprint "eagle-import:TACTILE-PTH")
      (libsource (lib "eagle-import") (part "TAC_SWITCHPTH"))
    )
    (comp (ref "SW2")
      (value "TAC_SWITCHPTH")
      (footprint "eagle-import:TACTILE-PTH")
      (libsource (lib "eagle-import") (part "TAC_SWITCHPTH"))
    )
    (comp (ref "SW3")
      (value "TAC_SWITCHPTH")
      (footprint "eagle-import:TACTILE-PTH")
      (libsource (lib "eagle-import") (part "TAC_SWITCHPTH"))
    )
  )
  (nets
    (net (code "1") (name "+3V3") (class "Default")
      (node (ref "C1") (pin "1") (pinfunction "1_1") (pintype "passive"))
      (node (ref "C10") (pin "+") (pinfunction "+_+") (pintype "passive"))
      (node (ref "C15") (pin "1") (pinfunction "1_1") (pintype "passive"))
      (node (ref "C16") (pin "1") (pinfunction "1_1") (pintype "passive"))
      (node (ref "C3") (pin "1") (pinfunction "1_1") (pintype "passive"))
      (node (ref "C6") (pin "1") (pinfunction "1_1") (pintype "passive"))
      (node (ref "C7") (pin "1") (pinfunction "1_1") (pintype "passive"))
      (node (ref "IC1") (pin "1") (pinfunction "VBAT_1") (pintype "power_in"))
      (node (ref "IC1") (pin "17") (pinfunction "VDD_2_17") (pintype "power_in"))
      (node (ref "IC1") (pin "48") (pinfunction "VDD_1_48") (pintype "power_in"))
      (node (ref "IC3") (pin "3") (pinfunction "VO_3") (pintype "passive"))
      (node (ref "IC4") (pin "12") (pinfunction "DVDD_12") (pintype "power_in"))
      (node (ref "R3") (pin "1") (pinfunction "1_1") (pintype "passive"))
    )
    (net (code "2") (name "+3V3_A") (class "Default")
      (node (ref "C12") (pin "1") (pinfunction "1_1") (pintype "passive"))
      (node (ref "C13") (pin "1") (pinfunction "1_1") (pintype "passive"))
      (node (ref "C14") (pin "1") (pinfunction "1_1") (pintype "passive"))
      (node (ref "C17") (pin "1") (pinfunction "1_1") (pintype "passive"))
      (node (ref "C29") (pin "+") (pinfunction "+_+") (pintype "passive"))
      (node (ref "C30") (pin "1") (pinfunction "1_1") (pintype "passive"))
      (node (ref "C43") (pin "1") (pinfunction "1_1") (pintype "passive"))
      (node (ref "C5") (pin "1") (pinfunction "1_1") (pintype "passive"))
      (node (ref "C50") (pin "+") (pinfunction "+_+") (pintype "passive"))
      (node (ref "C8") (pin "1") (pinfunction "1_1") (pintype "passive"))
      (node (ref "C9") (pin "+") (pinfunction "+_+") (pintype "passive"))
      (node (ref "D2") (pin "2") (pinfunction "C_2") (pintype "passive"))
      (node (ref "IC1") (pin "24") (pinfunction "VDDSD_24") (pintype "power_in"))
      (node (ref "IC1") (pin "25") (pinfunction "VREFSD+_25") (pintype "power_in"))
      (node (ref "IC1") (pin "9") (pinfunction "VDDA_9") (pintype "power_in"))
      (node (ref "IC2") (pin "16") (pinfunction "VCC_16") (pintype "power_in"))
      (node (ref "IC4") (pin "4") (pinfunction "AVDD_4") (pintype "power_in"))
      (node (ref "IC5") (pin "1") (pinfunction "VO_1") (pintype "passive"))
      (node (ref "IC6") (pin "4") (pinfunction "V+_4") (pintype "power_in"))
      (node (ref "IC7") (pin "4") (pinfunction "V+_4") (pintype "power_in"))
      (node (ref "R11") (pin "P$1") (pinfunction "E_P$1") (pintype "passive"))
      (node (ref "R12") (pin "P$1") (pinfunction "E_P$1") (pintype "passive"))
      (node (ref "R22") (pin "P$1") (pinfunction "E_P$1") (pintype "passive"))
      (node (ref "R23") (pin "P$1") (pinfunction "E_P$1") (pintype "passive"))
      (node (ref "R24") (pin "P$1") (pinfunction "E_P$1") (pintype "passive"))
      (node (ref "R56") (pin "P$1") (pinfunction "E_P$1") (pintype "passive"))
      (node (ref "R57") (pin "P$1") (pinfunction "E_P$1") (pintype "passive"))
      (node (ref "R58") (pin "P$1") (pinfunction "E_P$1") (pintype "passive"))
      (node (ref "R59") (pin "P$1") (pinfunction "E_P$1") (pintype "passive"))
      (node (ref "R60") (pin "P$1") (pinfunction "E_P$1") (pintype "passive"))
    )
    (net (code "3") (name "ADC_CLOCK") (class "Default")
      (node (ref "C36") (pin "2") (pinfunction "2_2") (pintype "passive"))
      (node (ref "IC1") (pin "20") (pinfunction "PB2/SDADC1_AIN4P/SDADC2_AIN6P_20") (pintype "bidirectional"))
      (node (ref "IC7") (pin "1") (pinfunction "OUT_1") (pintype "output"))
      (node (ref "R37") (pin "1") (pinfunction "1_1") (pintype "passive"))
    )
    (net (code "4") (name "ADC_FM") (class "Default")
      (node (ref "C46") (pin "2") (pinfunction "2_2") (pintype "passive"))
      (node (ref "IC1") (pin "21") (pinfunction "PE8/SDADC1_AIN8P/SDADC2_AIN8P_21") (pintype "bidirectional"))
      (node (ref "IC7") (pin "7") (pinfunction "OUT_7") (pintype "output"))
      (node (ref "R52") (pin "1") (pinfunction "1_1") (pintype "passive"))
    )
    (net (code "5") (name "ADC_SHAPE") (class "Default")
      (node (ref "C32") (pin "2") (pinfunction "2_2") (pintype "passive"))
      (node (ref "IC1") (pin "27") (pinfunction "PB15/SPI2_MOSI/I2S2_SD/SDADC3_AIN7P/SDADC3_AIN8M_27") (pintype "bidirectional"))
      (node (ref "IC6") (pin "8") (pinfunction "OUT_8") (pintype "output"))
      (node (ref "R27") (pin "1") (pinfunction "1_1") (pintype "passive"))
    )
    (net (code "6") (name "ADC_SHIFT") (class "Default")
      (node (ref "C28") (pin "2") (pinfunction "2_2") (pintype "passive"))
      (node (ref "IC1") (pin "28") (pinfunction "PD8/SPI2_SCK/I2S2_CK/USART3_TX/SDADC3_AIN6P_28") (pintype "bidirectional"))
      (node (ref "IC6") (pin "14") (pinfunction "OUT_14") (pintype "output"))
      (node (ref "R19") (pin "1") (pinfunction "1_1") (pintype "passive"))
    )
    (net (code "7") (name "ADC_SLOPE") (class "Default")
      (node (ref "C27") (pin "2") (pinfunction "2_2") (pintype "passive"))
      (node (ref "IC1") (pin "18") (pinfunction "PB0/SPI1_MOSI/I2S1_SD/TIM3_CH3/ADC_IN8/SDADC1_AIN6P_18") (pintype "bidirectional"))
      (node (ref "IC6") (pin "1") (pinfunction "OUT_1") (pintype "output"))
      (node (ref "R18") (pin "1") (pinfunction "1_1") (pintype "passive"))
    )
    (net (code "8") (name "ADC_SMOOTHNESS") (class "Default")
      (node (ref "C41") (pin "2") (pinfunction "2_2") (pintype "passive"))
      (node (ref "IC1") (pin "26") (pinfunction "PB14/SPI2_MISO/I2S2_MCK/USART3_RTS/SDADC3_AIN8P_26") (pintype "bidirectional"))
      (node (ref "IC7") (pin "14") (pinfunction "OUT_14") (pintype "output"))
      (node (ref "R41") (pin "1") (pinfunction "1_1") (pintype "passive"))
    )
    (net (code "9") (name "ADC_TRIG") (class "Default")
      (node (ref "C31") (pin "2") (pinfunction "2_2") (pintype "passive"))
      (node (ref "IC1") (pin "19") (pinfunction "PB1/TIM3_CH4/ADC_IN9/SDADC1_AIN5P/SDADC1_AIN6M_19") (pintype "bidirectional"))
      (node (ref "IC6") (pin "7") (pinfunction "OUT_7") (pintype "output"))
      (node (ref "R28") (pin "1") (pinfunction "1_1") (pintype "passive"))
    )
    (net (code "10") (name "ADC_V_OCT") (class "Default")
      (node (ref "C47") (pin "2") (pinfunction "2_2") (pintype "passive"))
      (node (ref "IC1") (pin "22") (pinfunction "PE9/SDADC1_AIN7P/SDADC1_AIN8M/SDADC2_AIN7P/SDADC2_AIN8M_22") (pintype "bidirectional"))
      (node (ref "IC7") (pin "8") (pinfunction "OUT_8") (pintype "output"))
      (node (ref "R53") (pin "1") (pinfunction "1_1") (pintype "passive"))
    )
    (net (code "11") (name "AREF_-10") (class "Default")
      (node (ref "C42") (pin "1") (pinfunction "1_1") (pintype "passive"))
      (node (ref "IC10") (pin "2") (pinfunction "A_2") (pintype "passive"))
      (node (ref "R20") (pin "2") (pinfunction "2_2") (pintype "passive"))
      (node (ref "R21") (pin "2") (pinfunction "2_2") (pintype "passive"))
      (node (ref "R25") (pin "2") (pinfunction "2_2") (pintype "passive"))
      (node (ref "R26") (pin "2") (pinfunction "2_2") (pintype "passive"))
      (node (ref "R43") (pin "2") (pinfunction "2_2") (pintype "passive"))
      (node (ref "R44") (pin "2") (pinfunction "2_2") (pintype "passive"))
      (node (ref "R46") (pin "2") (pinfunction "2_2") (pintype "passive"))
      (node (ref "R50") (pin "2") (pinfunction "2_2") (pintype "passive"))
      (node (ref "R51") (pin "2") (pinfunction "2_2") (pintype "passive"))
    )
    (net (code "12") (name "DAC_1") (class "Default")
      (node (ref "IC4") (pin "1") (pinfunction "OUTA_1") (pintype "output"))
      (node (ref "R31") (pin "2") (pinfunction "2_2") (pintype "passive"))
    )
    (net (code "13") (name "DAC_2") (class "Default")
      (node (ref "IC4") (pin "2") (pinfunction "OUTB_2") (pintype "output"))
      (node (ref "R32") (pin "2") (pinfunction "2_2") (pintype "passive"))
    )
    (net (code "14") (name "DAC_3") (class "Default")
      (node (ref "IC4") (pin "7") (pinfunction "OUTC_7") (pintype "output"))
      (node (ref "R33") (pin "2") (pinfunction "2_2") (pintype "passive"))
    )
    (net (code "15") (name "DAC_4") (class "Default")
      (node (ref "IC4") (pin "8") (pinfunction "OUTD_8") (pintype "output"))
      (node (ref "R34") (pin "2") (pinfunction "2_2") (pintype "passive"))
    )
    (net (code "16") (name "DAC_MOSI") (class "Default")
      (node (ref "IC1") (pin "31") (pinfunction "PA10/SPI2_MOSI/I2S2_SD/I2C2_SDA/USART1_RX/TIM2_CH4_31") (pintype "bidirectional"))
      (node (ref "IC4") (pin "11") (pinfunction "IN_11") (pintype "input"))
    )
    (net (code "17") (name "DAC_SCK") (class "Default")
      (node (ref "IC1") (pin "29") (pinfunction "PA8/SPI2_SCK/I2S2_CK/I2C2_SMBA/USART1_CK/TIM5_CH1_29") (pintype "bidirectional"))
      (node (ref "IC4") (pin "10") (pinfunction "SCK_10") (pintype "input"))
    )
    (net (code "18") (name "DAC_SS") (class "Default")
      (node (ref "IC1") (pin "32") (pinfunction "PA11/SPI2_NSS/I2S2_WS/SPI1_NSS/I2S1_WS/USART1_CTS/CAN_RX/TIM4_CH1/TIM5_CH2_32") (pintype "bidirectional"))
      (node (ref "IC4") (pin "9") (pinfunction "SYNC_9") (pintype "input"))
    )
    (net (code "19") (name "FREQUENCY_ATT") (class "Default")
      (node (ref "C52") (pin "1") (pinfunction "1_1") (pintype "passive"))
      (node (ref "IC2") (pin "2") (pinfunction "X6_2") (pintype "bidirectional"))
      (node (ref "R57") (pin "P$2") (pinfunction "S_P$2") (pintype "passive"))
    )
    (net (code "20") (name "FREQUENCY_POT") (class "Default")
      (node (ref "C22") (pin "1") (pinfunction "1_1") (pintype "passive"))
      (node (ref "IC1") (pin "16") (pinfunction "PA6/SPI1_MISO/I2S1_MCK/TIM3_CH1/ADC_IN6/DAC2_OUT1_16") (pintype "bidirectional"))
      (node (ref "R11") (pin "P$2") (pinfunction "S_P$2") (pintype "passive"))
    )
    (net (code "21") (name "GND") (class "Default")
      (node (ref "C1") (pin "2") (pinfunction "2_2") (pintype "passive"))
      (node (ref "C10") (pin "-") (pinfunction "-_-") (pintype "passive"))
      (node (ref "C11") (pin "1") (pinfunction "1_1") (pintype "passive"))
      (node (ref "C12") (pin "2") (pinfunction "2_2") (pintype "passive"))
      (node (ref "C13") (pin "2") (pinfunction "2_2") (pintype "passive"))
      (node (ref "C14") (pin "2") (pinfunction "2_2") (pintype "passive"))
      (node (ref "C15") (pin "2") (pinfunction "2_2") (pintype "passive"))
      (node (ref "C16") (pin "2") (pinfunction "2_2") (pintype "passive"))
      (node (ref "C17") (pin "2") (pinfunction "2_2") (pintype "passive"))
      (node (ref "C18") (pin "2") (pinfunction "2_2") (pintype "passive"))
      (node (ref "C19") (pin "2") (pinfunction "2_2") (pintype "passive"))
      (node (ref "C2") (pin "2") (pinfunction "2_2") (pintype "passive"))
      (node (ref "C20") (pin "2") (pinfunction "2_2") (pintype "passive"))
      (node (ref "C21") (pin "2") (pinfunction "2_2") (pintype "passive"))
      (node (ref "C22") (pin "2") (pinfunction "2_2") (pintype "passive"))
      (node (ref "C23") (pin "2") (pinfunction "2_2") (pintype "passive"))
      (node (ref "C24") (pin "-") (pinfunction "-_-") (pintype "passive"))
      (node (ref "C25") (pin "2") (pinfunction "2_2") (pintype "passive"))
      (node (ref "C26") (pin "+") (pinfunction "+_+") (pintype "passive"))
      (node (ref "C29") (pin "-") (pinfunction "-_-") (pintype "passive"))
      (node (ref "C3") (pin "2") (pinfunction "2_2") (pintype "passive"))
      (node (ref "C30") (pin "2") (pinfunction "2_2") (pintype "passive"))
      (node (ref "C33") (pin "1") (pinfunction "1_1") (pintype "passive"))
      (node (ref "C34") (pin "1") (pinfunction "1_1") (pintype "passive"))
      (node (ref "C35") (pin "2") (pinfunction "2_2") (pintype "passive"))
      (node (ref "C4") (pin "1") (pinfunction "1_1") (pintype "passive"))
      (node (ref "C42") (pin "2") (pinfunction "2_2") (pintype "passive"))
      (node (ref "C43") (pin "2") (pinfunction "2_2") (pintype "passive"))
      (node (ref "C44") (pin "2") (pinfunction "2_2") (pintype "passive"))
      (node (ref "C45") (pin "2") (pinfunction "2_2") (pintype "passive"))
      (node (ref "C48") (pin "2") (pinfunction "2_2") (pintype "passive"))
      (node (ref "C49") (pin "2") (pinfunction "2_2") (pintype "passive"))
      (node (ref "C5") (pin "2") (pinfunction "2_2") (pintype "passive"))
      (node (ref "C50") (pin "-") (pinfunction "-_-") (pintype "passive"))
      (node (ref "C51") (pin "2") (pinfunction "2_2") (pintype "passive"))
      (node (ref "C52") (pin "2") (pinfunction "2_2") (pintype "passive"))
      (node (ref "C53") (pin "2") (pinfunction "2_2") (pintype "passive"))
      (node (ref "C54") (pin "2") (pinfunction "2_2") (pintype "passive"))
      (node (ref "C55") (pin "2") (pinfunction "2_2") (pintype "passive"))
      (node (ref "C56") (pin "2") (pinfunction "2_2") (pintype "passive"))
      (node (ref "C6") (pin "2") (pinfunction "2_2") (pintype "passive"))
      (node (ref "C7") (pin "2") (pinfunction "2_2") (pintype "passive"))
      (node (ref "C8") (pin "2") (pinfunction "2_2") (pintype "passive"))
      (node (ref "C9") (pin "-") (pinfunction "-_-") (pintype "passive"))
      (node (ref "D10") (pin "1") (pinfunction "A_1") (pintype "passive"))
      (node (ref "D11") (pin "1") (pinfunction "A_1") (pintype "passive"))
      (node (ref "D2") (pin "1") (pinfunction "A_1") (pintype "passive"))
      (node (ref "D4") (pin "1") (pinfunction "A_1") (pintype "passive"))
      (node (ref "D5") (pin "1") (pinfunction "A_1") (pintype "passive"))
      (node (ref "D6") (pin "1") (pinfunction "A_1") (pintype "passive"))
      (node (ref "D7") (pin "1") (pinfunction "A_1") (pintype "passive"))
      (node (ref "D8") (pin "1") (pinfunction "A_1") (pintype "passive"))
      (node (ref "D9") (pin "1") (pinfunction "A_1") (pintype "passive"))
      (node (ref "IC1") (pin "23") (pinfunction "VSSSD/VREFSD-_23") (pintype "power_in"))
      (node (ref "IC1") (pin "44") (pinfunction "BOOT0_44") (pintype "bidirectional"))
      (node (ref "IC1") (pin "47") (pinfunction "VSS_1_47") (pintype "power_in"))
      (node (ref "IC1") (pin "8") (pinfunction "VSSA_8") (pintype "power_in"))
      (node (ref "IC10") (pin "1") (pinfunction "C_1") (pintype "passive"))
      (node (ref "IC2") (pin "6") (pinfunction "INH_6") (pintype "input"))
      (node (ref "IC2") (pin "7") (pinfunction "VEE_7") (pintype "power_in"))
      (node (ref "IC2") (pin "8") (pinfunction "GND_8") (pintype "power_in"))
      (node (ref "IC3") (pin "2") (pinfunction "GND_2") (pintype "passive"))
      (node (ref "IC4") (pin "13") (pinfunction "A0_13") (pintype "input"))
      (node (ref "IC4") (pin "14") (pinfunction "A1_14") (pintype "input"))
      (node (ref "IC4") (pin "15") (pinfunction "ENABLE_15") (pintype "input"))
      (node (ref "IC4") (pin "16") (pinfunction "LDAC_16") (pintype "input"))
      (node (ref "IC4") (pin "5") (pinfunction "VREFL_5") (pintype "bidirectional"))
      (node (ref "IC4") (pin "6") (pinfunction "GND_6") (pintype "power_in"))
      (node (ref "IC5") (pin "2") (pinfunction "GND_2") (pintype "passive"))
      (node (ref "IC6") (pin "10") (pinfunction "+IN_10") (pintype "input"))
      (node (ref "IC6") (pin "11") (pinfunction "V-_11") (pintype "power_in"))
      (node (ref "IC6") (pin "12") (pinfunction "+IN_12") (pintype "input"))
      (node (ref "IC6") (pin "3") (pinfunction "+IN_3") (pintype "input"))
      (node (ref "IC6") (pin "5") (pinfunction "+IN_5") (pintype "input"))
      (node (ref "IC7") (pin "10") (pinfunction "+IN_10") (pintype "input"))
      (node (ref "IC7") (pin "11") (pinfunction "V-_11") (pintype "power_in"))
      (node (ref "IC7") (pin "12") (pinfunction "+IN_12") (pintype "input"))
      (node (ref "IC7") (pin "3") (pinfunction "+IN_3") (pintype "input"))
      (node (ref "IC7") (pin "5") (pinfunction "+IN_5") (pintype "input"))
      (node (ref "J1") (pin "P1") (pinfunction "1_P1") (pintype "passive"))
      (node (ref "J1") (pin "P2") (pinfunction "2_P2") (pintype "passive"))
      (node (ref "J10") (pin "P1") (pinfunction "1_P1") (pintype "passive"))
      (node (ref "J11") (pin "P1") (pinfunction "1_P1") (pintype "passive"))
      (node (ref "J12") (pin "P1") (pinfunction "1_P1") (pintype "passive"))
      (node (ref "J2") (pin "P1") (pinfunction "1_P1") (pintype "passive"))
      (node (ref "J3") (pin "P1") (pinfunction "1_P1") (pintype "passive"))
      (node (ref "J3") (pin "P2") (pinfunction "2_P2") (pintype "passive"))
      (node (ref "J4") (pin "P1") (pinfunction "1_P1") (pintype "passive"))
      (node (ref "J4") (pin "P2") (pinfunction "2_P2") (pintype "passive"))
      (node (ref "J5") (pin "P1") (pinfunction "1_P1") (pintype "passive"))
      (node (ref "J5") (pin "P2") (pinfunction "2_P2") (pintype "passive"))
      (node (ref "J6") (pin "P1") (pinfunction "1_P1") (pintype "passive"))
      (node (ref "J6") (pin "P2") (pinfunction "2_P2") (pintype "passive"))
      (node (ref "J7") (pin "P1") (pinfunction "1_P1") (pintype "passive"))
      (node (ref "J8") (pin "P1") (pinfunction "1_P1") (pintype "passive"))
      (node (ref "J9") (pin "P1") (pinfunction "1_P1") (pintype "passive"))
      (node (ref "JP5") (pin "3") (pinfunction "3_3") (pintype "passive"))
      (node (ref "JP5") (pin "4") (pinfunction "4_4") (pintype "passive"))
      (node (ref "JP5") (pin "5") (pinfunction "5_5") (pintype "passive"))
      (node (ref "JP5") (pin "6") (pinfunction "6_6") (pintype "passive"))
      (node (ref "JP5") (pin "7") (pinfunction "7_7") (pintype "passive"))
      (node (ref "JP5") (pin "8") (pinfunction "8_8") (pintype "passive"))
      (node (ref "JP6") (pin "1") (pinfunction "1_1") (pintype "passive"))
      (node (ref "LED1") (pin "2") (pinfunction "C_2") (pintype "bidirectional"))
      (node (ref "LED2") (pin "2") (pinfunction "C_2") (pintype "bidirectional"))
      (node (ref "LED3") (pin "2") (pinfunction "C_2") (pintype "bidirectional"))
      (node (ref "Q1") (pin "2") (pinfunction "LID1_2") (pintype "power_in"))
      (node (ref "Q1") (pin "4") (pinfunction "LID2_4") (pintype "power_in"))
      (node (ref "R11") (pin "P$3") (pinfunction "A_P$3") (pintype "passive"))
      (node (ref "R12") (pin "P$3") (pinfunction "A_P$3") (pintype "passive"))
      (node (ref "R15") (pin "1") (pinfunction "1_1") (pintype "passive"))
      (node (ref "R22") (pin "P$3") (pinfunction "A_P$3") (pintype "passive"))
      (node (ref "R23") (pin "P$3") (pinfunction "A_P$3") (pintype "passive"))
      (node (ref "R24") (pin "P$3") (pinfunction "A_P$3") (pintype "passive"))
      (node (ref "R56") (pin "P$3") (pinfunction "A_P$3") (pintype "passive"))
      (node (ref "R57") (pin "P$3") (pinfunction "A_P$3") (pintype "passive"))
      (node (ref "R58") (pin "P$3") (pinfunction "A_P$3") (pintype "passive"))
      (node (ref "R59") (pin "P$3") (pinfunction "A_P$3") (pintype "passive"))
      (node (ref "R60") (pin "P$3") (pinfunction "A_P$3") (pintype "passive"))
      (node (ref "R64") (pin "2") (pinfunction "2_2") (pintype "passive"))
      (node (ref "R65") (pin "2") (pinfunction "2_2") (pintype "passive"))
      (node (ref "R66") (pin "2") (pinfunction "2_2") (pintype "passive"))
      (node (ref "R67") (pin "2") (pinfunction "2_2") (pintype "passive"))
      (node (ref "SW1") (pin "1") (pinfunction "1_1") (pintype "passive"))
      (node (ref "SW1") (pin "2") (pinfunction "2_2") (pintype "passive"))
      (node (ref "SW2") (pin "1") (pinfunction "1_1") (pintype "passive"))
      (node (ref "SW2") (pin "2") (pinfunction "2_2") (pintype "passive"))
      (node (ref "SW3") (pin "1") (pinfunction "1_1") (pintype "passive"))
      (node (ref "SW3") (pin "2") (pinfunction "2_2") (pintype "passive"))
    )
    (net (code "22") (name "LED_MODE_G") (class "Default")
      (node (ref "IC1") (pin "35") (pinfunction "PF6/SPI1_MOSI/I2S1_SD/USART3_RTS/TIM4_CH4/I2C2_SCL_35") (pintype "bidirectional"))
      (node (ref "R10") (pin "1") (pinfunction "1_1") (pintype "passive"))
    )
    (net (code "23") (name "LED_MODE_R") (class "Default")
      (node (ref "IC1") (pin "36") (pinfunction "PF7/I2C2_SDA/USART2_CK_36") (pintype "bidirectional"))
      (node (ref "R13") (pin "1") (pinfunction "1_1") (pintype "passive"))
    )
    (net (code "24") (name "LED_RANGE_G") (class "Default")
      (node (ref "IC1") (pin "42") (pinfunction "PB6/I2C1_SCL/USART1_TX/TIM4_CH1_42") (pintype "bidirectional"))
      (node (ref "R6") (pin "1") (pinfunction "1_1") (pintype "passive"))
    )
    (net (code "25") (name "LED_RANGE_R") (class "Default")
      (node (ref "IC1") (pin "41") (pinfunction "PB5/SPI1_MOSI/I2S1_SD/SPI3_MOSI/I2S3_SD/I2C1_SMBAI/USART2_CK/TIM3_CH2_41") (pintype "bidirectional"))
      (node (ref "R1") (pin "1") (pinfunction "1_1") (pintype "passive"))
    )
    (net (code "26") (name "LED_SHIFT_G") (class "Default")
      (node (ref "IC1") (pin "40") (pinfunction "PB4/SPI1_MISO/I2S1_MCK/SPI3_MISO/I2S3_MCK/USART2_RX/TIM3_CH1/NJTRST_40") (pintype "bidirectional"))
      (node (ref "R2") (pin "1") (pinfunction "1_1") (pintype "passive"))
    )
    (net (code "27") (name "LED_SHIFT_R") (class "Default")
      (node (ref "IC1") (pin "39") (pinfunction "PB3/SPI1_SCK/I2S1_CK/SPI3_SCK/I2S3_CK/USART2_TX/TIM2_CH2/JTDO/SPI3_SCK/JTDO_39") (pintype "bidirectional"))
      (node (ref "R7") (pin "1") (pinfunction "1_1") (pintype "passive"))
    )
    (net (code "28") (name "MUXED_POTS") (class "Default")
      (node (ref "C56") (pin "1") (pinfunction "1_1") (pintype "passive"))
      (node (ref "IC1") (pin "11") (pinfunction "PA1/SPI3_SCK/I2S3_CK/USART2_RTS/TIM2_CH2/TIM5_CH2/ADC_IN1_11") (pintype "bidirectional"))
      (node (ref "IC2") (pin "3") (pinfunction "X_3") (pintype "bidirectional"))
    )
    (net (code "29") (name "MUX_ADDR_0") (class "Default")
      (node (ref "IC1") (pin "13") (pinfunction "PA3/SPI3_MOSI/I2S3_SD/USART2_RX/TIM2_CH4/TIM5_CH4/ADC_IN3_13") (pintype "bidirectional"))
      (node (ref "IC2") (pin "11") (pinfunction "A_11") (pintype "input"))
    )
    (net (code "30") (name "MUX_ADDR_1") (class "Default")
      (node (ref "IC1") (pin "14") (pinfunction "PA4/SPI1_NSS/I2S1_WS/SPI3_NSS/I2S3_WS/USART2_CK/TIM3_CH2/ADC_IN4/DAC1_OUT1_14") (pintype "bidirectional"))
      (node (ref "IC2") (pin "10") (pinfunction "B_10") (pintype "input"))
    )
    (net (code "31") (name "MUX_ADDR_2") (class "Default")
      (node (ref "IC1") (pin "15") (pinfunction "PA5/SPI1_SCK/I2S1_CK/TIM2_CH1/ADC_IN5/DAC1_OUT2_15") (pintype "bidirectional"))
      (node (ref "IC2") (pin "9") (pinfunction "C_9") (pintype "input"))
    )
    (net (code "32") (name "NORMALIZATION_PROBE") (class "Default")
      (node (ref "D2") (pin "3") (pinfunction "AC_3") (pintype "passive"))
      (node (ref "IC1") (pin "30") (pinfunction "PA9/SPI_MISO/I2S2_MCK/I2C2_SCL/USART1_TX/TIM2_CH3_30") (pintype "bidirectional"))
      (node (ref "R61") (pin "2") (pinfunction "2_2") (pintype "passive"))
      (node (ref "R62") (pin "2") (pinfunction "2_2") (pintype "passive"))
      (node (ref "R63") (pin "2") (pinfunction "2_2") (pintype "passive"))
    )
    (net (code "33") (name "Net-(C11-Pad2)") (class "Default")
      (node (ref "C11") (pin "2") (pinfunction "2_2") (pintype "passive"))
      (node (ref "Q1") (pin "1") (pinfunction "1_1") (pintype "passive"))
      (node (ref "R9") (pin "2") (pinfunction "2_2") (pintype "passive"))
    )
    (net (code "34") (name "Net-(C20-Pad1)") (class "Default")
      (node (ref "C20") (pin "1") (pinfunction "1_1") (pintype "passive"))
      (node (ref "D1") (pin "C") (pinfunction "C_C") (pintype "passive"))
      (node (ref "L1") (pin "1") (pinfunction "1_1") (pintype "passive"))
      (node (ref "L2") (pin "2") (pinfunction "2_2") (pintype "passive"))
      (node (ref "L3") (pin "2") (pinfunction "2_2") (pintype "passive"))
    )
    (net (code "35") (name "Net-(D1-PadA)") (class "Default")
      (node (ref "D1") (pin "A") (pinfunction "A_A") (pintype "passive"))
      (node (ref "JP5") (pin "10") (pinfunction "10_10") (pintype "passive"))
      (node (ref "JP5") (pin "9") (pinfunction "9_9") (pintype "passive"))
    )
    (net (code "36") (name "Net-(D3-PadA)") (class "Default")
      (node (ref "D3") (pin "A") (pinfunction "A_A") (pintype "passive"))
      (node (ref "L4") (pin "2") (pinfunction "2_2") (pintype "passive"))
    )
    (net (code "37") (name "Net-(D3-PadC)") (class "Default")
      (node (ref "D3") (pin "C") (pinfunction "C_C") (pintype "passive"))
      (node (ref "JP5") (pin "1") (pinfunction "1_1") (pintype "passive"))
      (node (ref "JP5") (pin "2") (pinfunction "2_2") (pintype "passive"))
    )
    (net (code "38") (name "Net-(D4-C)") (class "Default")
      (node (ref "D4") (pin "2") (pinfunction "C_2") (pintype "passive"))
      (node (ref "J5") (pin "P3") (pinfunction "3_P3") (pintype "passive"))
      (node (ref "R30") (pin "2") (pinfunction "2_2") (pintype "passive"))
    )
    (net (code "39") (name "Net-(D5-C)") (class "Default")
      (node (ref "D5") (pin "2") (pinfunction "C_2") (pintype "passive"))
      (node (ref "J6") (pin "P3") (pinfunction "3_P3") (pintype "passive"))
      (node (ref "R17") (pin "2") (pinfunction "2_2") (pintype "passive"))
    )
    (net (code "40") (name "Net-(D6-C)") (class "Default")
      (node (ref "D6") (pin "2") (pinfunction "C_2") (pintype "passive"))
      (node (ref "J4") (pin "P3") (pinfunction "3_P3") (pintype "passive"))
      (node (ref "R36") (pin "2") (pinfunction "2_2") (pintype "passive"))
    )
    (net (code "41") (name "Net-(D7-C)") (class "Default")
      (node (ref "D7") (pin "2") (pinfunction "C_2") (pintype "passive"))
      (node (ref "J3") (pin "P3") (pinfunction "3_P3") (pintype "passive"))
      (node (ref "R54") (pin "2") (pinfunction "2_2") (pintype "passive"))
    )
    (net (code "42") (name "Net-(D8-C)") (class "Default")
      (node (ref "D8") (pin "2") (pinfunction "C_2") (pintype "passive"))
      (node (ref "J1") (pin "P3") (pinfunction "3_P3") (pintype "passive"))
      (node (ref "R16") (pin "2") (pinfunction "2_2") (pintype "passive"))
    )
    (net (code "43") (name "Net-(D9-C)") (class "Default")
      (node (ref "D9") (pin "2") (pinfunction "C_2") (pintype "passive"))
      (node (ref "J2") (pin "P3") (pinfunction "3_P3") (pintype "passive"))
      (node (ref "R55") (pin "2") (pinfunction "2_2") (pintype "passive"))
    )
    (net (code "44") (name "Net-(D10-C)") (class "Default")
      (node (ref "D10") (pin "2") (pinfunction "C_2") (pintype "passive"))
      (node (ref "J7") (pin "P3") (pinfunction "3_P3") (pintype "passive"))
      (node (ref "R29") (pin "2") (pinfunction "2_2") (pintype "passive"))
    )
    (net (code "45") (name "Net-(D11-C)") (class "Default")
      (node (ref "D11") (pin "2") (pinfunction "C_2") (pintype "passive"))
      (node (ref "J8") (pin "P3") (pinfunction "3_P3") (pintype "passive"))
      (node (ref "R35") (pin "2") (pinfunction "2_2") (pintype "passive"))
    )
    (net (code "46") (name "Net-(IC1-PF0{slash}OSC_IN{slash}I2C2_SDA)") (class "Default")
      (node (ref "IC1") (pin "5") (pinfunction "PF0/OSC_IN/I2C2_SDA_5") (pintype "bidirectional"))
      (node (ref "R8") (pin "1") (pinfunction "1_1") (pintype "passive"))
    )
    (net (code "47") (name "Net-(IC1-PF1{slash}OSC_OUT{slash}I2C2_SCL)") (class "Default")
      (node (ref "IC1") (pin "6") (pinfunction "PF1/OSC_OUT/I2C2_SCL_6") (pintype "bidirectional"))
      (node (ref "R9") (pin "1") (pinfunction "1_1") (pintype "passive"))
    )
    (net (code "48") (name "Net-(IC3-VI)") (class "Default")
      (node (ref "C19") (pin "1") (pinfunction "1_1") (pintype "passive"))
      (node (ref "IC3") (pin "1") (pinfunction "VI_1") (pintype "input"))
      (node (ref "L1") (pin "2") (pinfunction "2_2") (pintype "passive"))
    )
    (net (code "49") (name "Net-(IC5-VI)") (class "Default")
      (node (ref "C25") (pin "1") (pinfunction "1_1") (pintype "passive"))
      (node (ref "IC5") (pin "3") (pinfunction "VI_3") (pintype "input"))
      (node (ref "L3") (pin "1") (pinfunction "1_1") (pintype "passive"))
    )
    (net (code "50") (name "Net-(IC6A--IN)") (class "Default")
      (node (ref "C27") (pin "1") (pinfunction "1_1") (pintype "passive"))
      (node (ref "IC6") (pin "2") (pinfunction "-IN_2") (pintype "input"))
      (node (ref "R16") (pin "1") (pinfunction "1_1") (pintype "passive"))
      (node (ref "R18") (pin "2") (pinfunction "2_2") (pintype "passive"))
      (node (ref "R20") (pin "1") (pinfunction "1_1") (pintype "passive"))
    )
    (net (code "51") (name "Net-(IC6B--IN)") (class "Default")
      (node (ref "C31") (pin "1") (pinfunction "1_1") (pintype "passive"))
      (node (ref "IC6") (pin "6") (pinfunction "-IN_6") (pintype "input"))
      (node (ref "R26") (pin "1") (pinfunction "1_1") (pintype "passive"))
      (node (ref "R28") (pin "2") (pinfunction "2_2") (pintype "passive"))
      (node (ref "R29") (pin "1") (pinfunction "1_1") (pintype "passive"))
    )
    (net (code "52") (name "Net-(IC6C--IN)") (class "Default")
      (node (ref "C32") (pin "1") (pinfunction "1_1") (pintype "passive"))
      (node (ref "IC6") (pin "9") (pinfunction "-IN_9") (pintype "input"))
      (node (ref "R25") (pin "1") (pinfunction "1_1") (pintype "passive"))
      (node (ref "R27") (pin "2") (pinfunction "2_2") (pintype "passive"))
      (node (ref "R30") (pin "1") (pinfunction "1_1") (pintype "passive"))
    )
    (net (code "53") (name "Net-(IC6D--IN)") (class "Default")
      (node (ref "C28") (pin "1") (pinfunction "1_1") (pintype "passive"))
      (node (ref "IC6") (pin "13") (pinfunction "-IN_13") (pintype "input"))
      (node (ref "R17") (pin "1") (pinfunction "1_1") (pintype "passive"))
      (node (ref "R19") (pin "2") (pinfunction "2_2") (pintype "passive"))
      (node (ref "R21") (pin "1") (pinfunction "1_1") (pintype "passive"))
    )
    (net (code "54") (name "Net-(IC7A--IN)") (class "Default")
      (node (ref "C36") (pin "1") (pinfunction "1_1") (pintype "passive"))
      (node (ref "IC7") (pin "2") (pinfunction "-IN_2") (pintype "input"))
      (node (ref "R35") (pin "1") (pinfunction "1_1") (pintype "passive"))
      (node (ref "R37") (pin "2") (pinfunction "2_2") (pintype "passive"))
      (node (ref "R44") (pin "1") (pinfunction "1_1") (pintype "passive"))
    )
    (net (code "55") (name "Net-(IC7B--IN)") (class "Default")
      (node (ref "C46") (pin "1") (pinfunction "1_1") (pintype "passive"))
      (node (ref "IC7") (pin "6") (pinfunction "-IN_6") (pintype "input"))
      (node (ref "R51") (pin "1") (pinfunction "1_1") (pintype "passive"))
      (node (ref "R52") (pin "2") (pinfunction "2_2") (pintype "passive"))
      (node (ref "R55") (pin "1") (pinfunction "1_1") (pintype "passive"))
    )
    (net (code "56") (name "Net-(IC7C--IN)") (class "Default")
      (node (ref "C47") (pin "1") (pinfunction "1_1") (pintype "passive"))
      (node (ref "IC7") (pin "9") (pinfunction "-IN_9") (pintype "input"))
      (node (ref "R50") (pin "1") (pinfunction "1_1") (pintype "passive"))
      (node (ref "R53") (pin "2") (pinfunction "2_2") (pintype "passive"))
      (node (ref "R54") (pin "1") (pinfunction "1_1") (pintype "passive"))
    )
    (net (code "57") (name "Net-(IC7D--IN)") (class "Default")
      (node (ref "C41") (pin "1") (pinfunction "1_1") (pintype "passive"))
      (node (ref "IC7") (pin "13") (pinfunction "-IN_13") (pintype "input"))
      (node (ref "R36") (pin "1") (pinfunction "1_1") (pintype "passive"))
      (node (ref "R41") (pin "2") (pinfunction "2_2") (pintype "passive"))
      (node (ref "R43") (pin "1") (pinfunction "1_1") (pintype "passive"))
    )
    (net (code "58") (name "Net-(IC8A-+IN)") (class "Default")
      (node (ref "C39") (pin "2") (pinfunction "2_2") (pintype "passive"))
      (node (ref "IC8") (pin "14") (pinfunction "OUT_14") (pintype "output"))
      (node (ref "IC8") (pin "3") (pinfunction "+IN_3") (pintype "input"))
      (node (ref "R48") (pin "2") (pinfunction "2_2") (pintype "passive"))
    )
    (net (code "59") (name "Net-(IC8A--IN)") (class "Default")
      (node (ref "IC8") (pin "2") (pinfunction "-IN_2") (pintype "input"))
      (node (ref "LED6") (pin "2") (pinfunction "2_2") (pintype "bidirectional"))
      (node (ref "R66") (pin "1") (pinfunction "1_1") (pintype "passive"))
    )
    (net (code "60") (name "Net-(IC8A-OUT)") (class "Default")
      (node (ref "IC8") (pin "1") (pinfunction "OUT_1") (pintype "output"))
      (node (ref "LED6") (pin "1") (pinfunction "1_1") (pintype "bidirectional"))
    )
    (net (code "61") (name "Net-(IC8B-+IN)") (class "Default")
      (node (ref "C40") (pin "2") (pinfunction "2_2") (pintype "passive"))
      (node (ref "IC8") (pin "5") (pinfunction "+IN_5") (pintype "input"))
      (node (ref "IC8") (pin "8") (pinfunction "OUT_8") (pintype "output"))
      (node (ref "R49") (pin "2") (pinfunction "2_2") (pintype "passive"))
    )
    (net (code "62") (name "Net-(IC8B--IN)") (class "Default")
      (node (ref "IC8") (pin "6") (pinfunction "-IN_6") (pintype "input"))
      (node (ref "LED7") (pin "2") (pinfunction "2_2") (pintype "bidirectional"))
      (node (ref "R67") (pin "1") (pinfunction "1_1") (pintype "passive"))
    )
    (net (code "63") (name "Net-(IC8B-OUT)") (class "Default")
      (node (ref "IC8") (pin "7") (pinfunction "OUT_7") (pintype "output"))
      (node (ref "LED7") (pin "1") (pinfunction "1_1") (pintype "bidirectional"))
    )
    (net (code "64") (name "Net-(IC8C--IN)") (class "Default")
      (node (ref "C40") (pin "1") (pinfunction "1_1") (pintype "passive"))
      (node (ref "IC8") (pin "9") (pinfunction "-IN_9") (pintype "input"))
      (node (ref "R34") (pin "1") (pinfunction "1_1") (pintype "passive"))
      (node (ref "R40") (pin "2") (pinfunction "2_2") (pintype "passive"))
    )
    (net (code "65") (name "Net-(IC8D--IN)") (class "Default")
      (node (ref "C39") (pin "1") (pinfunction "1_1") (pintype "passive"))
      (node (ref "IC8") (pin "13") (pinfunction "-IN_13") (pintype "input"))
      (node (ref "R33") (pin "1") (pinfunction "1_1") (pintype "passive"))
      (node (ref "R39") (pin "2") (pinfunction "2_2") (pintype "passive"))
    )
    (net (code "66") (name "Net-(IC9A-+IN)") (class "Default")
      (node (ref "C37") (pin "2") (pinfunction "2_2") (pintype "passive"))
      (node (ref "IC9") (pin "14") (pinfunction "OUT_14") (pintype "output"))
      (node (ref "IC9") (pin "3") (pinfunction "+IN_3") (pintype "input"))
      (node (ref "R47") (pin "2") (pinfunction "2_2") (pintype "passive"))
    )
    (net (code "67") (name "Net-(IC9A--IN)") (class "Default")
      (node (ref "IC9") (pin "2") (pinfunction "-IN_2") (pintype "input"))
      (node (ref "LED4") (pin "2") (pinfunction "2_2") (pintype "bidirectional"))
      (node (ref "R64") (pin "1") (pinfunction "1_1") (pintype "passive"))
    )
    (net (code "68") (name "Net-(IC9A-OUT)") (class "Default")
      (node (ref "IC9") (pin "1") (pinfunction "OUT_1") (pintype "output"))
      (node (ref "LED4") (pin "1") (pinfunction "1_1") (pintype "bidirectional"))
    )
    (net (code "69") (name "Net-(IC9B-+IN)") (class "Default")
      (node (ref "C38") (pin "2") (pinfunction "2_2") (pintype "passive"))
      (node (ref "IC9") (pin "5") (pinfunction "+IN_5") (pintype "input"))
      (node (ref "IC9") (pin "8") (pinfunction "OUT_8") (pintype "output"))
      (node (ref "R45") (pin "2") (pinfunction "2_2") (pintype "passive"))
    )
    (net (code "70") (name "Net-(IC9B--IN)") (class "Default")
      (node (ref "IC9") (pin "6") (pinfunction "-IN_6") (pintype "input"))
      (node (ref "LED5") (pin "2") (pinfunction "2_2") (pintype "bidirectional"))
      (node (ref "R65") (pin "1") (pinfunction "1_1") (pintype "passive"))
    )
    (net (code "71") (name "Net-(IC9B-OUT)") (class "Default")
      (node (ref "IC9") (pin "7") (pinfunction "OUT_7") (pintype "output"))
      (node (ref "LED5") (pin "1") (pinfunction "1_1") (pintype "bidirectional"))
    )
    (net (code "72") (name "Net-(IC9C--IN)") (class "Default")
      (node (ref "C38") (pin "1") (pinfunction "1_1") (pintype "passive"))
      (node (ref "IC9") (pin "9") (pinfunction "-IN_9") (pintype "input"))
      (node (ref "R32") (pin "1") (pinfunction "1_1") (pintype "passive"))
      (node (ref "R38") (pin "2") (pinfunction "2_2") (pintype "passive"))
    )
    (net (code "73") (name "Net-(IC9D--IN)") (class "Default")
      (node (ref "C37") (pin "1") (pinfunction "1_1") (pintype "passive"))
      (node (ref "IC9") (pin "13") (pinfunction "-IN_13") (pintype "input"))
      (node (ref "R31") (pin "1") (pinfunction "1_1") (pintype "passive"))
      (node (ref "R42") (pin "2") (pinfunction "2_2") (pintype "passive"))
    )
    (net (code "74") (name "Net-(J2-2)") (class "Default")
      (node (ref "J2") (pin "P2") (pinfunction "2_P2") (pintype "passive"))
      (node (ref "R61") (pin "1") (pinfunction "1_1") (pintype "passive"))
    )
    (net (code "75") (name "Net-(J7-2)") (class "Default")
      (node (ref "J7") (pin "P2") (pinfunction "2_P2") (pintype "passive"))
      (node (ref "R62") (pin "1") (pinfunction "1_1") (pintype "passive"))
    )
    (net (code "76") (name "Net-(J8-2)") (class "Default")
      (node (ref "J8") (pin "P2") (pinfunction "2_P2") (pintype "passive"))
      (node (ref "R63") (pin "1") (pinfunction "1_1") (pintype "passive"))
    )
    (net (code "77") (name "Net-(J9-3)") (class "Default")
      (node (ref "J9") (pin "P3") (pinfunction "3_P3") (pintype "passive"))
      (node (ref "R42") (pin "1") (pinfunction "1_1") (pintype "passive"))
      (node (ref "R47") (pin "1") (pinfunction "1_1") (pintype "passive"))
    )
    (net (code "78") (name "Net-(J10-3)") (class "Default")
      (node (ref "J10") (pin "P3") (pinfunction "3_P3") (pintype "passive"))
      (node (ref "R38") (pin "1") (pinfunction "1_1") (pintype "passive"))
      (node (ref "R45") (pin "1") (pinfunction "1_1") (pintype "passive"))
    )
    (net (code "79") (name "Net-(J11-3)") (class "Default")
      (node (ref "J11") (pin "P3") (pinfunction "3_P3") (pintype "passive"))
      (node (ref "R39") (pin "1") (pinfunction "1_1") (pintype "passive"))
      (node (ref "R48") (pin "1") (pinfunction "1_1") (pintype "passive"))
    )
    (net (code "80") (name "Net-(J12-3)") (class "Default")
      (node (ref "J12") (pin "P3") (pinfunction "3_P3") (pintype "passive"))
      (node (ref "R40") (pin "1") (pinfunction "1_1") (pintype "passive"))
      (node (ref "R49") (pin "1") (pinfunction "1_1") (pintype "passive"))
    )
    (net (code "81") (name "Net-(JP7-Pad1)") (class "Default")
      (node (ref "JP7") (pin "1") (pinfunction "1_1") (pintype "passive"))
      (node (ref "R4") (pin "1") (pinfunction "1_1") (pintype "passive"))
    )
    (net (code "82") (name "Net-(JP7-Pad2)") (class "Default")
      (node (ref "JP7") (pin "2") (pinfunction "2_2") (pintype "passive"))
      (node (ref "R5") (pin "1") (pinfunction "1_1") (pintype "passive"))
    )
    (net (code "83") (name "Net-(LED1-GRN)") (class "Default")
      (node (ref "LED1") (pin "1") (pinfunction "GRN_1") (pintype "bidirectional"))
      (node (ref "R6") (pin "2") (pinfunction "2_2") (pintype "passive"))
    )
    (net (code "84") (name "Net-(LED1-RED)") (class "Default")
      (node (ref "LED1") (pin "3") (pinfunction "RED_3") (pintype "bidirectional"))
      (node (ref "R1") (pin "2") (pinfunction "2_2") (pintype "passive"))
    )
    (net (code "85") (name "Net-(LED2-GRN)") (class "Default")
      (node (ref "LED2") (pin "1") (pinfunction "GRN_1") (pintype "bidirectional"))
      (node (ref "R2") (pin "2") (pinfunction "2_2") (pintype "passive"))
    )
    (net (code "86") (name "Net-(LED2-RED)") (class "Default")
      (node (ref "LED2") (pin "3") (pinfunction "RED_3") (pintype "bidirectional"))
      (node (ref "R7") (pin "2") (pinfunction "2_2") (pintype "passive"))
    )
    (net (code "87") (name "Net-(LED3-GRN)") (class "Default")
      (node (ref "LED3") (pin "1") (pinfunction "GRN_1") (pintype "bidirectional"))
      (node (ref "R10") (pin "2") (pinfunction "2_2") (pintype "passive"))
    )
    (net (code "88") (name "Net-(LED3-RED)") (class "Default")
      (node (ref "LED3") (pin "3") (pinfunction "RED_3") (pintype "bidirectional"))
      (node (ref "R13") (pin "2") (pinfunction "2_2") (pintype "passive"))
    )
    (net (code "89") (name "Net-(Q1B-2)") (class "Default")
      (node (ref "C4") (pin "2") (pinfunction "2_2") (pintype "passive"))
      (node (ref "Q1") (pin "3") (pinfunction "2_3") (pintype "passive"))
      (node (ref "R8") (pin "2") (pinfunction "2_2") (pintype "passive"))
    )
    (net (code "90") (name "RESET") (class "Default")
      (node (ref "C2") (pin "1") (pinfunction "1_1") (pintype "passive"))
      (node (ref "IC1") (pin "7") (pinfunction "NRST_7") (pintype "bidirectional"))
      (node (ref "JP6") (pin "4") (pinfunction "4_4") (pintype "passive"))
      (node (ref "R3") (pin "2") (pinfunction "2_2") (pintype "passive"))
    )
    (net (code "91") (name "RX") (class "Default")
      (node (ref "IC1") (pin "46") (pinfunction "PB9/SPI2_NSS/I2S2_WS/I2C1_SDA/USART3_RX/CAN_TX/TIM4_CH4_46") (pintype "bidirectional"))
      (node (ref "R4") (pin "2") (pinfunction "2_2") (pintype "passive"))
    )
    (net (code "92") (name "SHAPE_ATT") (class "Default")
      (node (ref "C54") (pin "1") (pinfunction "1_1") (pintype "passive"))
      (node (ref "IC2") (pin "4") (pinfunction "X7_4") (pintype "bidirectional"))
      (node (ref "R59") (pin "P$2") (pinfunction "S_P$2") (pintype "passive"))
    )
    (net (code "93") (name "SHAPE_POT") (class "Default")
      (node (ref "C23") (pin "1") (pinfunction "1_1") (pintype "passive"))
      (node (ref "IC1") (pin "10") (pinfunction "PA0/USART2_CTS/TIM2_CH1/TIM5_CH1/ADC_IN0_10") (pintype "bidirectional"))
      (node (ref "R12") (pin "P$2") (pinfunction "S_P$2") (pintype "passive"))
    )
    (net (code "94") (name "SHIFT_ATT") (class "Default")
      (node (ref "C55") (pin "1") (pinfunction "1_1") (pintype "passive"))
      (node (ref "IC2") (pin "15") (pinfunction "X2_15") (pintype "bidirectional"))
      (node (ref "R60") (pin "P$2") (pinfunction "S_P$2") (pintype "passive"))
    )
    (net (code "95") (name "SHIFT_POT") (class "Default")
      (node (ref "C45") (pin "1") (pinfunction "1_1") (pintype "passive"))
      (node (ref "IC2") (pin "14") (pinfunction "X1_14") (pintype "bidirectional"))
      (node (ref "R24") (pin "P$2") (pinfunction "S_P$2") (pintype "passive"))
    )
    (net (code "96") (name "SLOPE_ATT") (class "Default")
      (node (ref "C51") (pin "1") (pinfunction "1_1") (pintype "passive"))
      (node (ref "IC2") (pin "1") (pinfunction "X4_1") (pintype "bidirectional"))
      (node (ref "R56") (pin "P$2") (pinfunction "S_P$2") (pintype "passive"))
    )
    (net (code "97") (name "SLOPE_POT") (class "Default")
      (node (ref "C44") (pin "1") (pinfunction "1_1") (pintype "passive"))
      (node (ref "IC2") (pin "12") (pinfunction "X3_12") (pintype "bidirectional"))
      (node (ref "R23") (pin "P$2") (pinfunction "S_P$2") (pintype "passive"))
    )
    (net (code "98") (name "SMOOTHNESS_ATT") (class "Default")
      (node (ref "C53") (pin "1") (pinfunction "1_1") (pintype "passive"))
      (node (ref "IC2") (pin "5") (pinfunction "X5_5") (pintype "bidirectional"))
      (node (ref "R58") (pin "P$2") (pinfunction "S_P$2") (pintype "passive"))
    )
    (net (code "99") (name "SMOOTHNESS_POT") (class "Default")
      (node (ref "C35") (pin "1") (pinfunction "1_1") (pintype "passive"))
      (node (ref "IC2") (pin "13") (pinfunction "X0_13") (pintype "bidirectional"))
      (node (ref "R22") (pin "P$2") (pinfunction "S_P$2") (pintype "passive"))
    )
    (net (code "100") (name "SWCLK") (class "Default")
      (node (ref "IC1") (pin "37") (pinfunction "PA14/I2C1_SDA/JTCK-SWCLK_37") (pintype "bidirectional"))
      (node (ref "JP6") (pin "3") (pinfunction "3_3") (pintype "passive"))
    )
    (net (code "101") (name "SWDIO") (class "Default")
      (node (ref "IC1") (pin "34") (pinfunction "PA13/SPI1_MISO/I2S1_MCK/USART3_CTS/TIM4_CH3/TIM5_CH4/JTMS-SWDIO_34") (pintype "bidirectional"))
      (node (ref "JP6") (pin "2") (pinfunction "2_2") (pintype "passive"))
    )
    (net (code "102") (name "SW_MODE") (class "Default")
      (node (ref "IC1") (pin "33") (pinfunction "PA12/SPI1_SCK/I2S1_CK/USART1_RTS/CAN_TX/TIM4_CH2/TIM5_CH3_33") (pintype "bidirectional"))
      (node (ref "SW3") (pin "3") (pinfunction "3_3") (pintype "passive"))
      (node (ref "SW3") (pin "4") (pinfunction "4_4") (pintype "passive"))
    )
    (net (code "103") (name "SW_RANGE") (class "Default")
      (node (ref "IC1") (pin "12") (pinfunction "PA2/SPI3_MISO/I2S3_MCK/USART2_TX/TIM2_CH3/TIM5_CH3/ADC_IN2_12") (pintype "bidirectional"))
      (node (ref "SW2") (pin "3") (pinfunction "3_3") (pintype "passive"))
      (node (ref "SW2") (pin "4") (pinfunction "4_4") (pintype "passive"))
    )
    (net (code "104") (name "SW_SHIFT") (class "Default")
      (node (ref "IC1") (pin "2") (pinfunction "PC13/TIMESTAMP/RTC_TAMPER1_2") (pintype "bidirectional"))
      (node (ref "SW1") (pin "3") (pinfunction "3_3") (pintype "passive"))
      (node (ref "SW1") (pin "4") (pinfunction "4_4") (pintype "passive"))
    )
    (net (code "105") (name "TX") (class "Default")
      (node (ref "IC1") (pin "45") (pinfunction "PB8/SPI2_SCK/I2S2_CK/I2C1_SCL/USART3_TX/CAN_RX/TIM4_CH3_45") (pintype "bidirectional"))
      (node (ref "R5") (pin "2") (pinfunction "2_2") (pintype "passive"))
    )
    (net (code "106") (name "VCC") (class "Default")
      (node (ref "C24") (pin "+") (pinfunction "+_+") (pintype "passive"))
      (node (ref "C48") (pin "1") (pinfunction "1_1") (pintype "passive"))
      (node (ref "C49") (pin "1") (pinfunction "1_1") (pintype "passive"))
      (node (ref "IC8") (pin "4") (pinfunction "V+_4") (pintype "power_in"))
      (node (ref "IC9") (pin "4") (pinfunction "V+_4") (pintype "power_in"))
      (node (ref "L2") (pin "1") (pinfunction "1_1") (pintype "passive"))
    )
    (net (code "107") (name "VEE") (class "Default")
      (node (ref "C26") (pin "-") (pinfunction "-_-") (pintype "passive"))
      (node (ref "C33") (pin "2") (pinfunction "2_2") (pintype "passive"))
      (node (ref "C34") (pin "2") (pinfunction "2_2") (pintype "passive"))
      (node (ref "IC8") (pin "11") (pinfunction "V-_11") (pintype "power_in"))
      (node (ref "IC9") (pin "11") (pinfunction "V-_11") (pintype "power_in"))
      (node (ref "L4") (pin "1") (pinfunction "1_1") (pintype "passive"))
      (node (ref "R46") (pin "1") (pinfunction "1_1") (pintype "passive"))
    )
    (net (code "108") (name "VREF") (class "Default")
      (node (ref "C18") (pin "1") (pinfunction "1_1") (pintype "passive"))
      (node (ref "IC4") (pin "3") (pinfunction "VREFH_3") (pintype "bidirectional"))
      (node (ref "R14") (pin "2") (pinfunction "2_2") (pintype "passive"))
    )
    (net (code "109") (name "VREF_BIAS") (class "Default")
      (node (ref "C21") (pin "1") (pinfunction "1_1") (pintype "passive"))
      (node (ref "IC8") (pin "10") (pinfunction "+IN_10") (pintype "input"))
      (node (ref "IC8") (pin "12") (pinfunction "+IN_12") (pintype "input"))
      (node (ref "IC9") (pin "10") (pinfunction "+IN_10") (pintype "input"))
      (node (ref "IC9") (pin "12") (pinfunction "+IN_12") (pintype "input"))
      (node (ref "R14") (pin "1") (pinfunction "1_1") (pintype "passive"))
      (node (ref "R15") (pin "2") (pinfunction "2_2") (pintype "passive"))
    )
    (net (code "110") (name "unconnected-(IC1-PA15{slash}SPI1_NSS{slash}I2S1_WS{slash}SPI3_NSS{slash}I2S3_WS{slash}I2C1_SCL{slash}TIM2_CH1_ETR{slash}JTDI-Pad38)") (class "Default")
      (node (ref "IC1") (pin "38") (pinfunction "PA15/SPI1_NSS/I2S1_WS/SPI3_NSS/I2S3_WS/I2C1_SCL/TIM2_CH1_ETR/JTDI_38") (pintype "bidirectional"))
    )
    (net (code "111") (name "unconnected-(IC1-PB7{slash}I2C1_SDA{slash}USART1_RX{slash}TIM4_CH2-Pad43)") (class "Default")
      (node (ref "IC1") (pin "43") (pinfunction "PB7/I2C1_SDA/USART1_RX/TIM4_CH2_43") (pintype "bidirectional"))
    )
    (net (code "112") (name "unconnected-(IC1-PC14{slash}OSC32_IN-Pad3)") (class "Default")
      (node (ref "IC1") (pin "3") (pinfunction "PC14/OSC32_IN_3") (pintype "bidirectional"))
    )
    (net (code "113") (name "unconnected-(IC1-PC15{slash}OSC32_OUT-Pad4)") (class "Default")
      (node (ref "IC1") (pin "4") (pinfunction "PC15/OSC32_OUT_4") (pintype "bidirectional"))
    )
    (net (code "114") (name "unconnected-(J9-2-PadP2)") (class "Default")
      (node (ref "J9") (pin "P2") (pinfunction "2_P2") (pintype "passive"))
    )
    (net (code "115") (name "unconnected-(J10-2-PadP2)") (class "Default")
      (node (ref "J10") (pin "P2") (pinfunction "2_P2") (pintype "passive"))
    )
    (net (code "116") (name "unconnected-(J11-2-PadP2)") (class "Default")
      (node (ref "J11") (pin "P2") (pinfunction "2_P2") (pintype "passive"))
    )
    (net (code "117") (name "unconnected-(J12-2-PadP2)") (class "Default")
      (node (ref "J12") (pin "P2") (pinfunction "2_P2") (pintype "passive"))
    )
  )
)
